# DeMux3.net
KiCad netlist of a schematic drawn in EAGLE
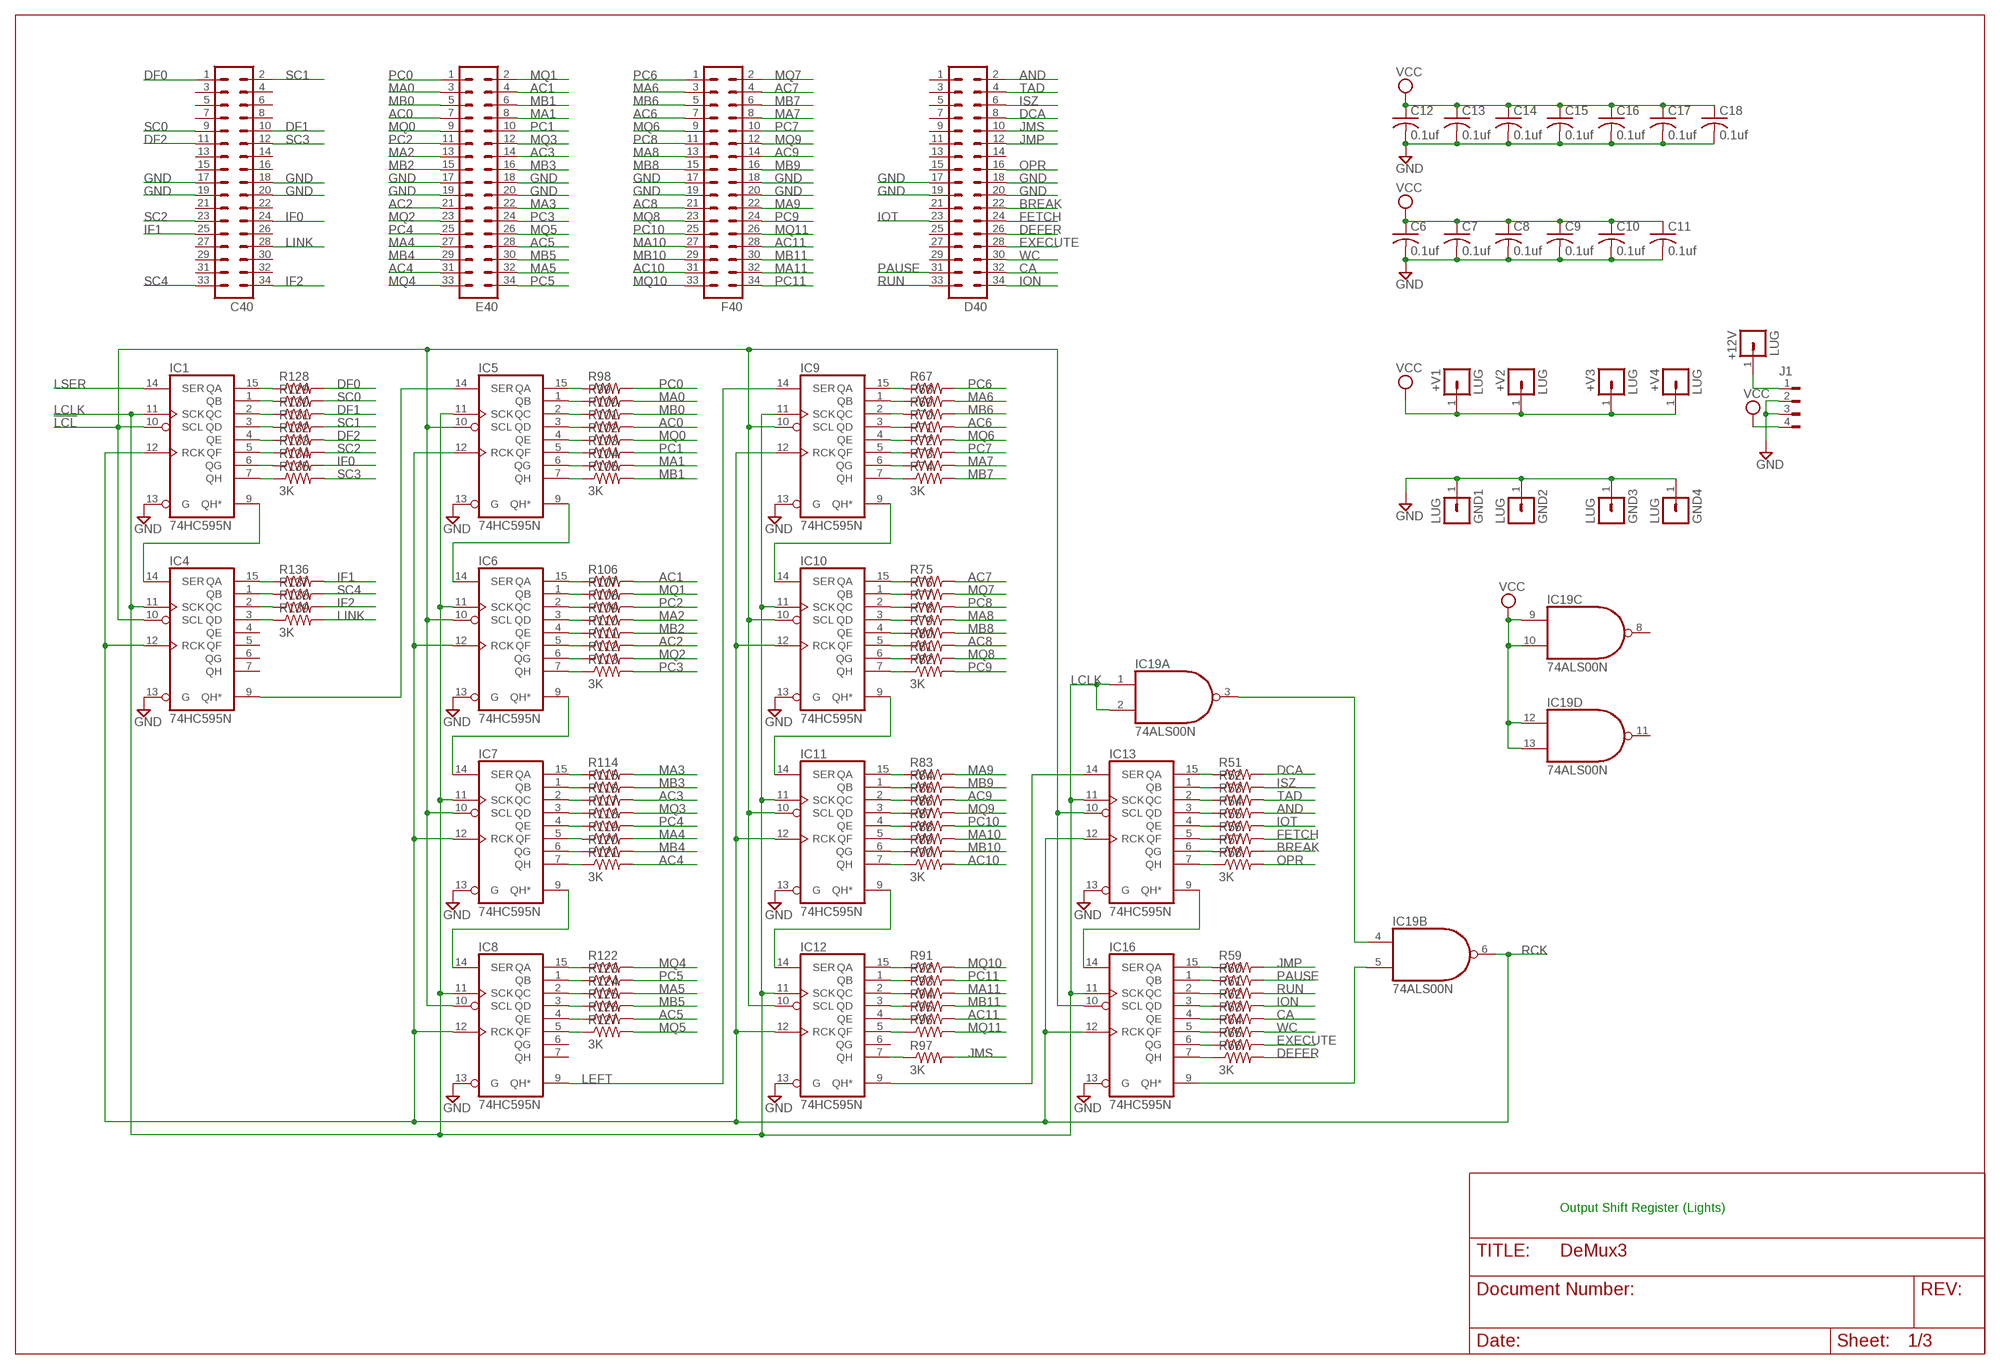
[diagram p0: schematic, sheet 1]
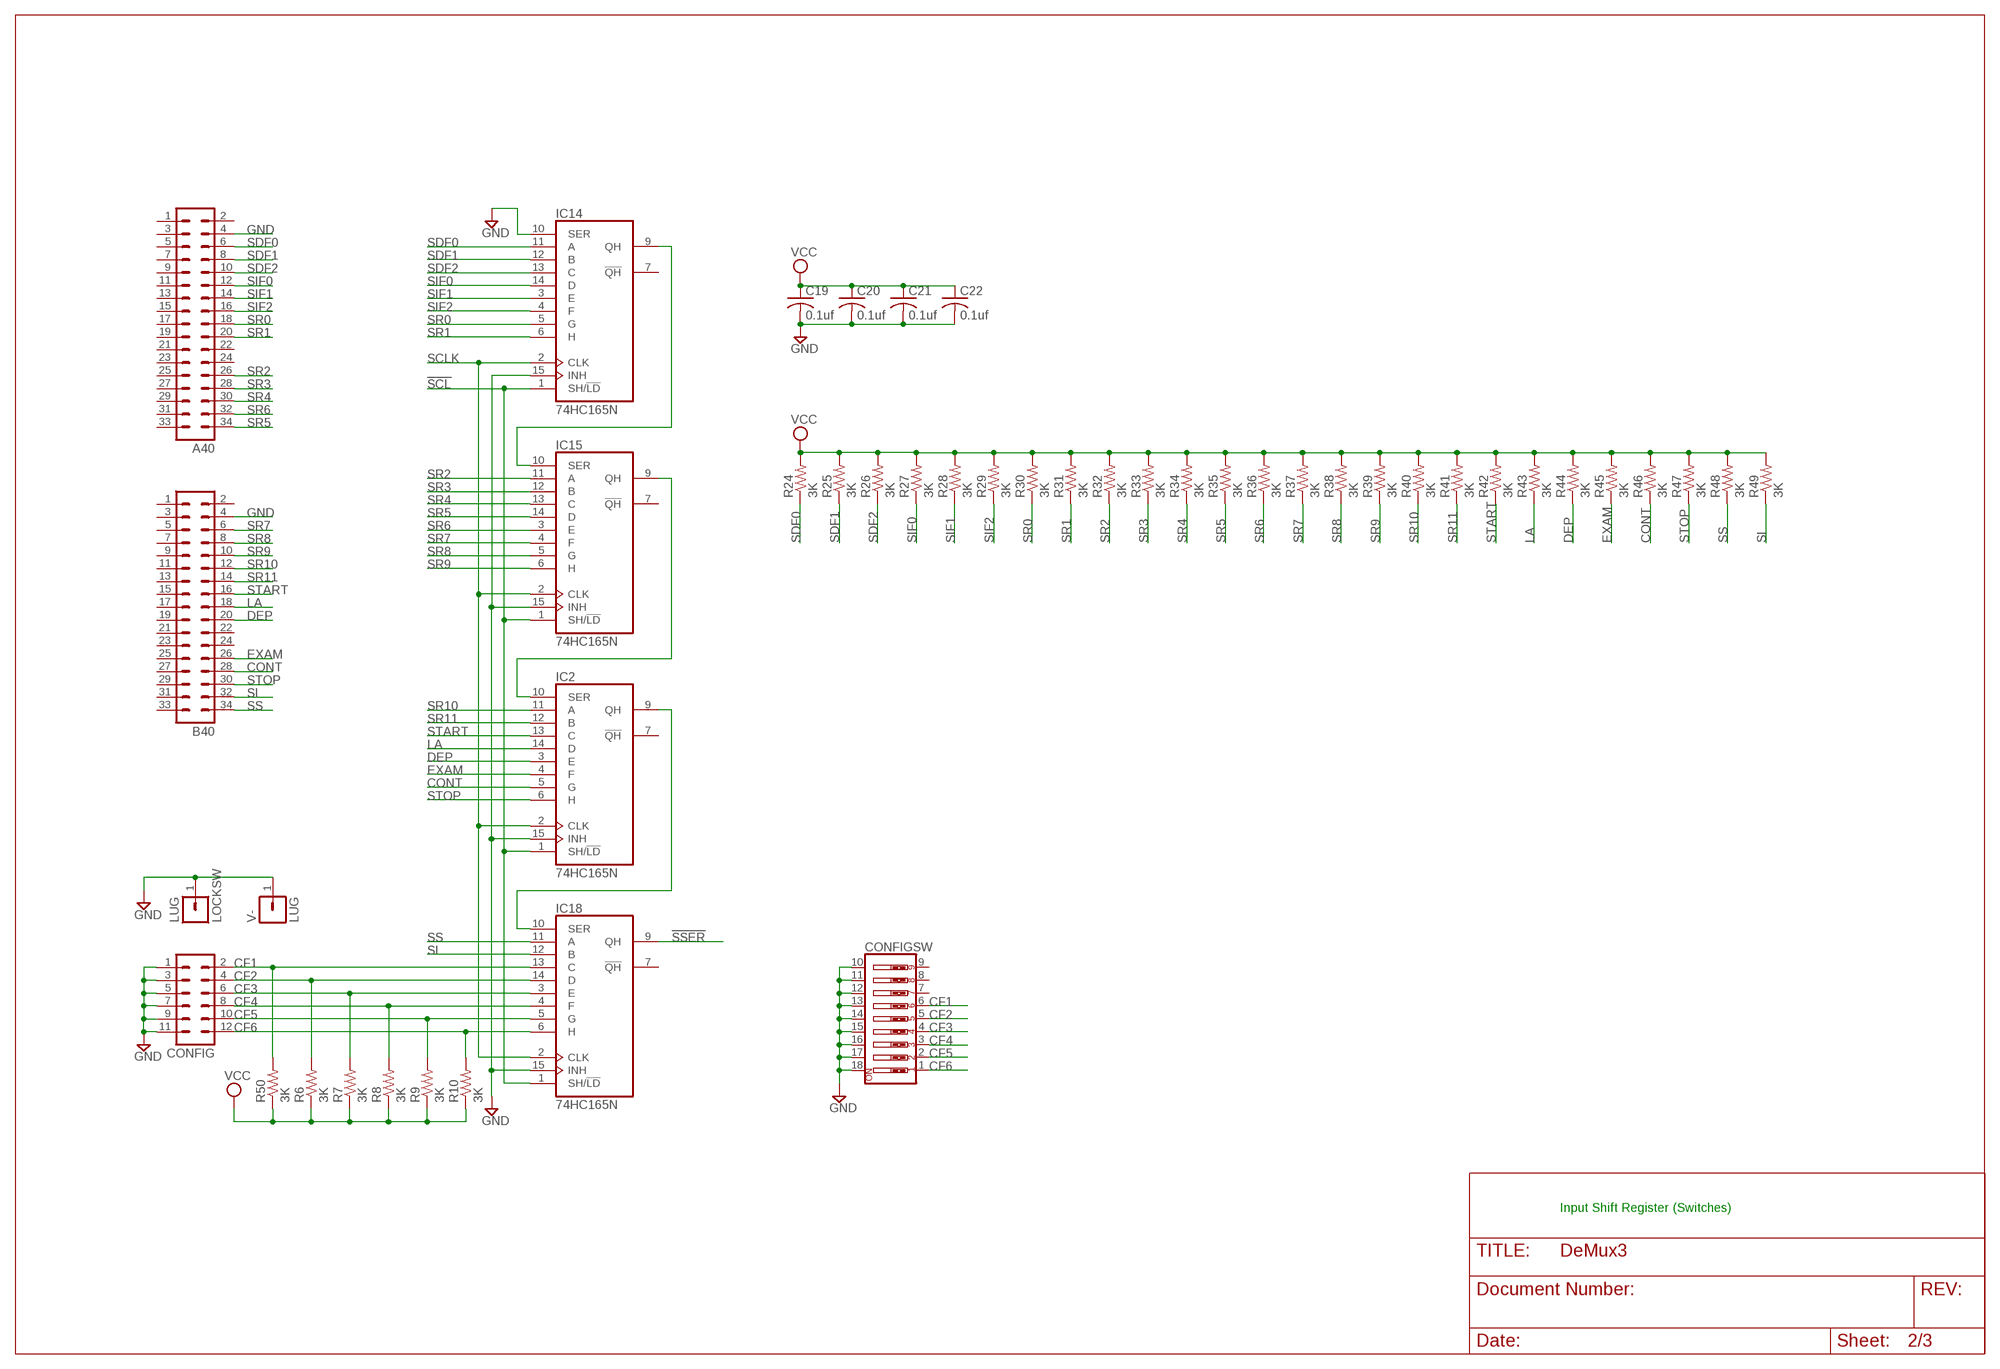
[diagram p1: schematic, sheet 2]
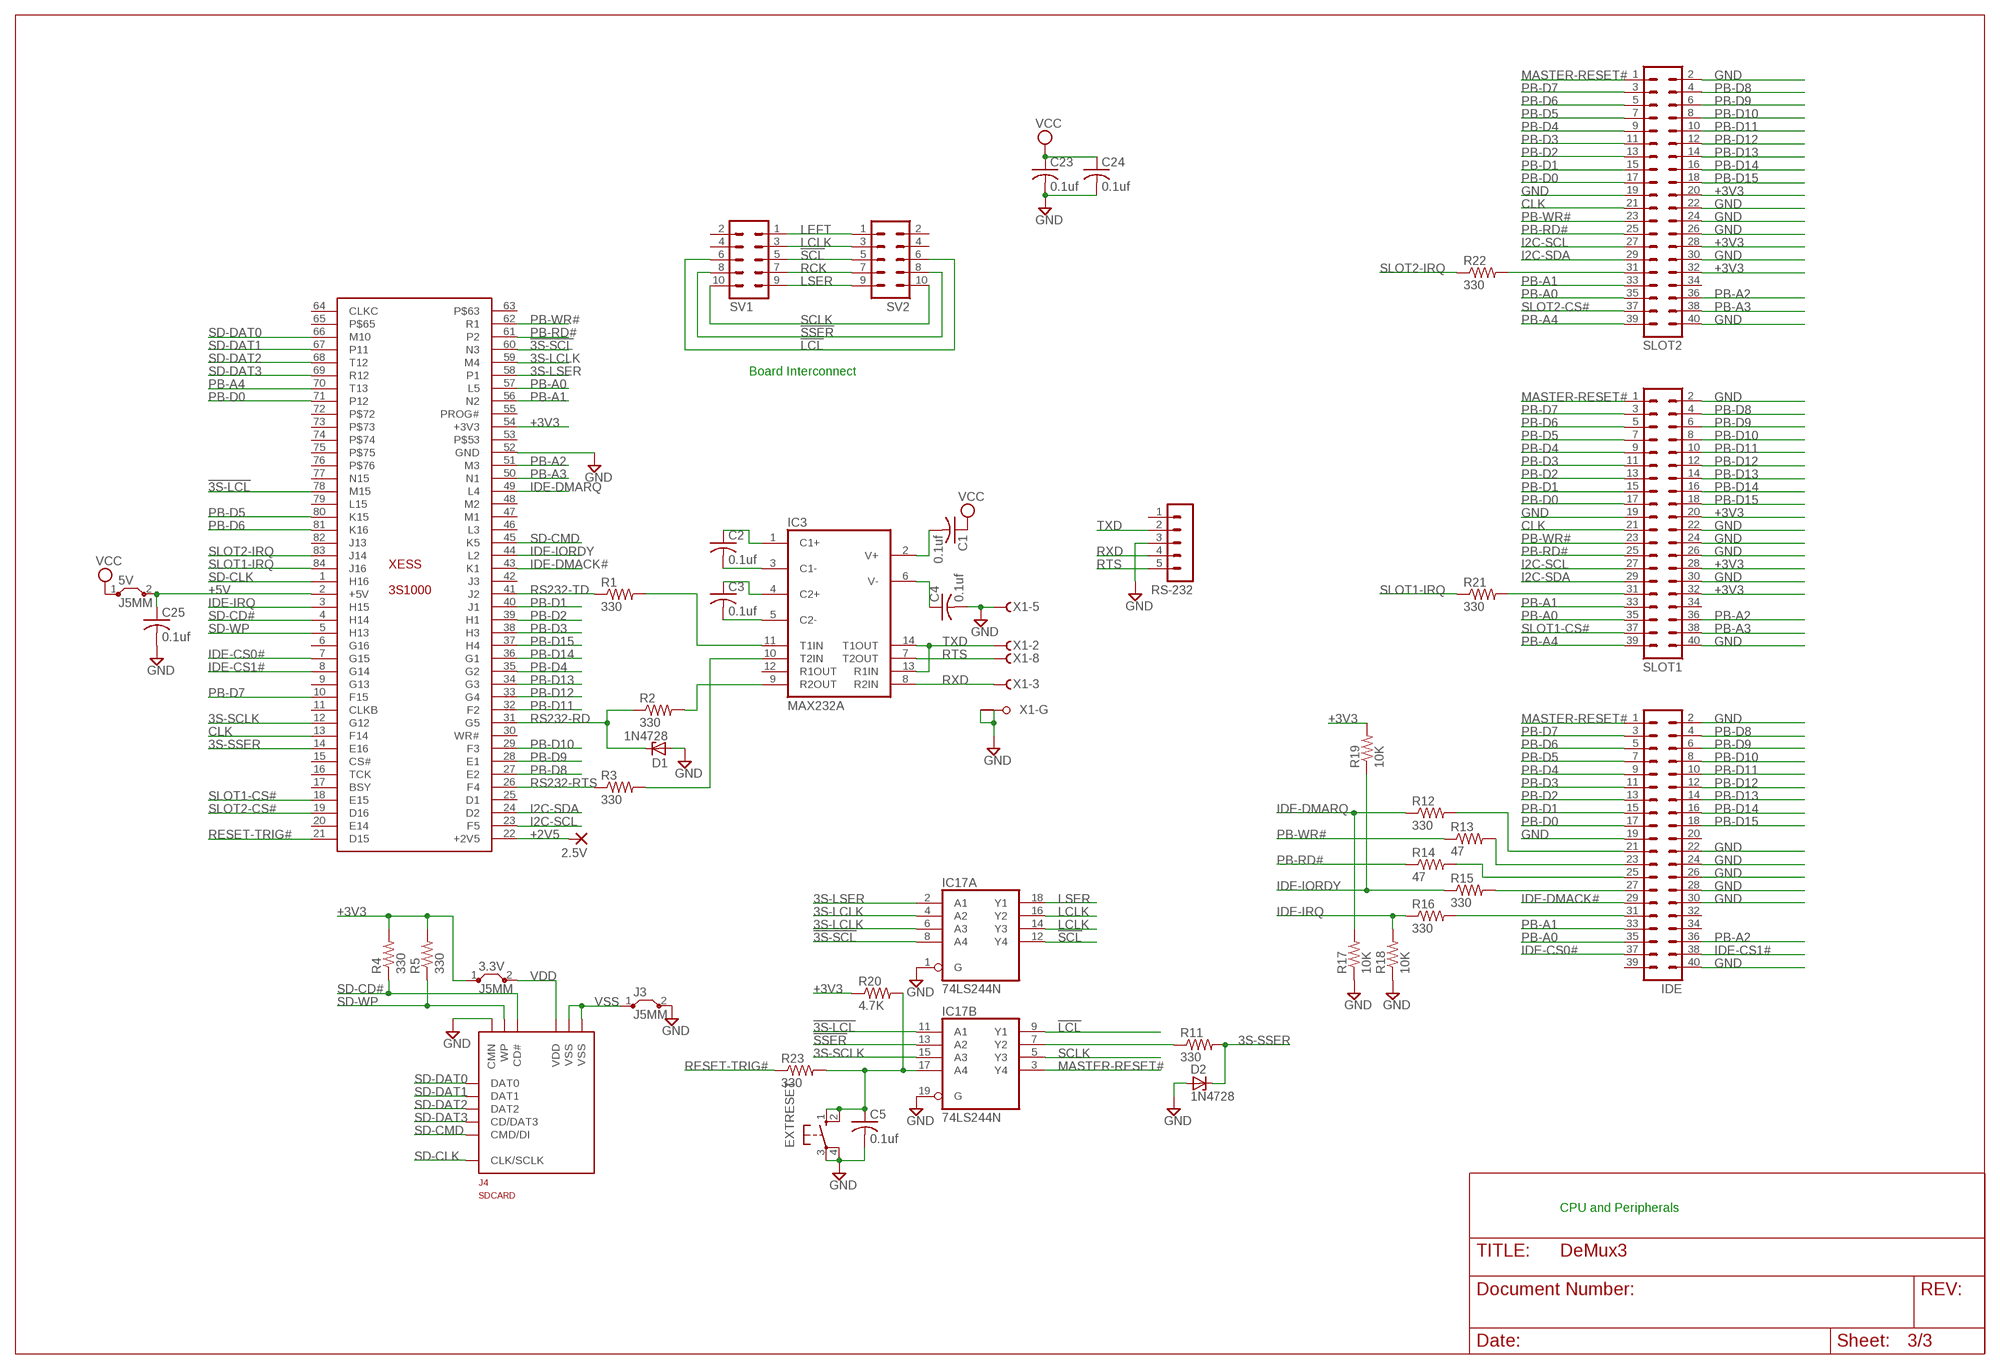
[diagram p2: schematic, sheet 3]

(export (version "E")
  (design (tool "Eeschema 10.0.6"))
  (components
    (comp (ref "2.5V")
      (value "1,6/0,8")
      (footprint "eagle-import:1,6_0,8")
      (libsource (lib "eagle-import") (part "1,6/0,8"))
    )
    (comp (ref "3.3V")
      (value "J5MM")
      (footprint "eagle-import:05")
      (libsource (lib "eagle-import") (part "J5MM"))
    )
    (comp (ref "5V")
      (value "J5MM")
      (footprint "eagle-import:05")
      (libsource (lib "eagle-import") (part "J5MM"))
    )
    (comp (ref "C1")
      (value "0.1uf")
      (footprint "eagle-import:C050-025X075")
      (libsource (lib "eagle-import") (part "C-US050-025X075"))
    )
    (comp (ref "C2")
      (value "0.1uf")
      (footprint "eagle-import:C050-025X075")
      (libsource (lib "eagle-import") (part "C-US050-025X075"))
    )
    (comp (ref "C3")
      (value "0.1uf")
      (footprint "eagle-import:C050-025X075")
      (libsource (lib "eagle-import") (part "C-US050-025X075"))
    )
    (comp (ref "C4")
      (value "0.1uf")
      (footprint "eagle-import:C050-025X075")
      (libsource (lib "eagle-import") (part "C-US050-025X075"))
    )
    (comp (ref "C5")
      (value "0.1uf")
      (footprint "eagle-import:C050-025X075")
      (libsource (lib "eagle-import") (part "C-US050-025X075"))
    )
    (comp (ref "C23")
      (value "0.1uf")
      (footprint "eagle-import:C050-025X075")
      (libsource (lib "eagle-import") (part "C-US050-025X075"))
    )
    (comp (ref "C24")
      (value "0.1uf")
      (footprint "eagle-import:C050-025X075")
      (libsource (lib "eagle-import") (part "C-US050-025X075"))
    )
    (comp (ref "C25")
      (value "0.1uf")
      (footprint "eagle-import:C050-025X075")
      (libsource (lib "eagle-import") (part "C-US050-025X075"))
    )
    (comp (ref "D1")
      (value "1N4728")
      (footprint "eagle-import:DO41Z10")
      (libsource (lib "eagle-import") (part "1N4728"))
    )
    (comp (ref "D2")
      (value "1N4728")
      (footprint "eagle-import:DO41Z10")
      (libsource (lib "eagle-import") (part "1N4728"))
    )
    (comp (ref "EXTRESET")
      (value "40-XX")
      (footprint "eagle-import:B3F-40XX")
      (fields (field (name "MF") "OMRON COMPONENTS USA") (field (name "MPN") "B3F-4000"))
      (libsource (lib "eagle-import") (part "40-XX"))
    )
    (comp (ref "IC3")
      (value "MAX232A")
      (footprint "eagle-import:DIL16")
      (fields (field (name "MF") "MAXIM") (field (name "MPN") "MAX232ACPE+"))
      (libsource (lib "eagle-import") (part "MAX232"))
    )
    (comp (ref "IC17")
      (value "74LS244N")
      (footprint "eagle-import:DIL20")
      (libsource (lib "eagle-import") (part "74244NLS"))
    )
    (comp (ref "IDE")
      (value "MA20-2")
      (footprint "eagle-import:MA20-2")
      (libsource (lib "eagle-import") (part "MA20-2"))
    )
    (comp (ref "J3")
      (value "J5MM")
      (footprint "eagle-import:05")
      (libsource (lib "eagle-import") (part "J5MM"))
    )
    (comp (ref "J4")
      (value "SDCARD")
      (footprint "eagle-import:SCDA5A")
      (libsource (lib "eagle-import") (part "SDCARD"))
    )
    (comp (ref "R1")
      (value "330")
      (footprint "eagle-import:0207_10")
      (libsource (lib "eagle-import") (part "R-US_0207/10"))
    )
    (comp (ref "R2")
      (value "330")
      (footprint "eagle-import:0207_10")
      (libsource (lib "eagle-import") (part "R-US_0207/10"))
    )
    (comp (ref "R3")
      (value "330")
      (footprint "eagle-import:0207_10")
      (libsource (lib "eagle-import") (part "R-US_0207/10"))
    )
    (comp (ref "R4")
      (value "330")
      (footprint "eagle-import:0207_10")
      (libsource (lib "eagle-import") (part "R-US_0207/10"))
    )
    (comp (ref "R5")
      (value "330")
      (footprint "eagle-import:0207_10")
      (libsource (lib "eagle-import") (part "R-US_0207/10"))
    )
    (comp (ref "R11")
      (value "330")
      (footprint "eagle-import:0207_10")
      (libsource (lib "eagle-import") (part "R-US_0207/10"))
    )
    (comp (ref "R12")
      (value "330")
      (footprint "eagle-import:0207_10")
      (libsource (lib "eagle-import") (part "R-US_0207/10"))
    )
    (comp (ref "R13")
      (value "47")
      (footprint "eagle-import:0207_10")
      (libsource (lib "eagle-import") (part "R-US_0207/10"))
    )
    (comp (ref "R14")
      (value "47")
      (footprint "eagle-import:0207_10")
      (libsource (lib "eagle-import") (part "R-US_0207/10"))
    )
    (comp (ref "R15")
      (value "330")
      (footprint "eagle-import:0207_10")
      (libsource (lib "eagle-import") (part "R-US_0207/10"))
    )
    (comp (ref "R16")
      (value "330")
      (footprint "eagle-import:0207_10")
      (libsource (lib "eagle-import") (part "R-US_0207/10"))
    )
    (comp (ref "R17")
      (value "10K")
      (footprint "eagle-import:0207_10")
      (libsource (lib "eagle-import") (part "R-US_0207/10"))
    )
    (comp (ref "R18")
      (value "10K")
      (footprint "eagle-import:0207_10")
      (libsource (lib "eagle-import") (part "R-US_0207/10"))
    )
    (comp (ref "R19")
      (value "10K")
      (footprint "eagle-import:0207_10")
      (libsource (lib "eagle-import") (part "R-US_0207/10"))
    )
    (comp (ref "R20")
      (value "4.7K")
      (footprint "eagle-import:0207_10")
      (libsource (lib "eagle-import") (part "R-US_0207/10"))
    )
    (comp (ref "R21")
      (value "330")
      (footprint "eagle-import:0207_10")
      (libsource (lib "eagle-import") (part "R-US_0207/10"))
    )
    (comp (ref "R22")
      (value "330")
      (footprint "eagle-import:0207_10")
      (libsource (lib "eagle-import") (part "R-US_0207/10"))
    )
    (comp (ref "R23")
      (value "330")
      (footprint "eagle-import:0207_10")
      (libsource (lib "eagle-import") (part "R-US_0207/10"))
    )
    (comp (ref "RS-232")
      (value "MA05-1")
      (footprint "eagle-import:MA05-1")
      (libsource (lib "eagle-import") (part "MA05-1"))
    )
    (comp (ref "SLOT1")
      (value "MA20-2")
      (footprint "eagle-import:MA20-2")
      (libsource (lib "eagle-import") (part "MA20-2"))
    )
    (comp (ref "SLOT2")
      (value "MA20-2")
      (footprint "eagle-import:MA20-2")
      (libsource (lib "eagle-import") (part "MA20-2"))
    )
    (comp (ref "SV1")
      (value "MA05-2")
      (footprint "eagle-import:MA05-2")
      (libsource (lib "eagle-import") (part "MA05-2"))
    )
    (comp (ref "SV2")
      (value "MA05-2")
      (footprint "eagle-import:MA05-2")
      (libsource (lib "eagle-import") (part "MA05-2"))
    )
    (comp (ref "X1")
      (value "F09HPS")
      (footprint "eagle-import:F09HP")
      (libsource (lib "eagle-import") (part "F09HPS"))
    )
    (comp (ref "XESS")
      (value "3S1000")
      (footprint "eagle-import:3S1000")
      (libsource (lib "eagle-import") (part "3S1000"))
    )
    (comp (ref "+12V")
      (value "LUG")
      (footprint "eagle-import:SPADELUG")
      (libsource (lib "eagle-import") (part "LUG"))
    )
    (comp (ref "+V1")
      (value "LUG")
      (footprint "eagle-import:SPADELUG")
      (libsource (lib "eagle-import") (part "LUG"))
    )
    (comp (ref "+V2")
      (value "LUG")
      (footprint "eagle-import:SPADELUG")
      (libsource (lib "eagle-import") (part "LUG"))
    )
    (comp (ref "+V3")
      (value "LUG")
      (footprint "eagle-import:SPADELUG")
      (libsource (lib "eagle-import") (part "LUG"))
    )
    (comp (ref "+V4")
      (value "LUG")
      (footprint "eagle-import:SPADELUG")
      (libsource (lib "eagle-import") (part "LUG"))
    )
    (comp (ref "C6")
      (value "0.1uf")
      (footprint "eagle-import:C050-025X075")
      (libsource (lib "eagle-import") (part "C-US050-025X075"))
    )
    (comp (ref "C7")
      (value "0.1uf")
      (footprint "eagle-import:C050-025X075")
      (libsource (lib "eagle-import") (part "C-US050-025X075"))
    )
    (comp (ref "C8")
      (value "0.1uf")
      (footprint "eagle-import:C050-025X075")
      (libsource (lib "eagle-import") (part "C-US050-025X075"))
    )
    (comp (ref "C9")
      (value "0.1uf")
      (footprint "eagle-import:C050-025X075")
      (libsource (lib "eagle-import") (part "C-US050-025X075"))
    )
    (comp (ref "C10")
      (value "0.1uf")
      (footprint "eagle-import:C050-025X075")
      (libsource (lib "eagle-import") (part "C-US050-025X075"))
    )
    (comp (ref "C11")
      (value "0.1uf")
      (footprint "eagle-import:C050-025X075")
      (libsource (lib "eagle-import") (part "C-US050-025X075"))
    )
    (comp (ref "C12")
      (value "0.1uf")
      (footprint "eagle-import:C050-025X075")
      (libsource (lib "eagle-import") (part "C-US050-025X075"))
    )
    (comp (ref "C13")
      (value "0.1uf")
      (footprint "eagle-import:C050-025X075")
      (libsource (lib "eagle-import") (part "C-US050-025X075"))
    )
    (comp (ref "C14")
      (value "0.1uf")
      (footprint "eagle-import:C050-025X075")
      (libsource (lib "eagle-import") (part "C-US050-025X075"))
    )
    (comp (ref "C15")
      (value "0.1uf")
      (footprint "eagle-import:C050-025X075")
      (libsource (lib "eagle-import") (part "C-US050-025X075"))
    )
    (comp (ref "C16")
      (value "0.1uf")
      (footprint "eagle-import:C050-025X075")
      (libsource (lib "eagle-import") (part "C-US050-025X075"))
    )
    (comp (ref "C17")
      (value "0.1uf")
      (footprint "eagle-import:C050-025X075")
      (libsource (lib "eagle-import") (part "C-US050-025X075"))
    )
    (comp (ref "C18")
      (value "0.1uf")
      (footprint "eagle-import:C050-025X075")
      (libsource (lib "eagle-import") (part "C-US050-025X075"))
    )
    (comp (ref "C40")
      (value "MA17-2")
      (footprint "eagle-import:MA17-2")
      (libsource (lib "eagle-import") (part "MA17-2"))
    )
    (comp (ref "D40")
      (value "MA17-2")
      (footprint "eagle-import:MA17-2")
      (libsource (lib "eagle-import") (part "MA17-2"))
    )
    (comp (ref "E40")
      (value "MA17-2")
      (footprint "eagle-import:MA17-2")
      (libsource (lib "eagle-import") (part "MA17-2"))
    )
    (comp (ref "F40")
      (value "MA17-2")
      (footprint "eagle-import:MA17-2")
      (libsource (lib "eagle-import") (part "MA17-2"))
    )
    (comp (ref "GND1")
      (value "LUG")
      (footprint "eagle-import:SPADELUG")
      (libsource (lib "eagle-import") (part "LUG"))
    )
    (comp (ref "GND2")
      (value "LUG")
      (footprint "eagle-import:SPADELUG")
      (libsource (lib "eagle-import") (part "LUG"))
    )
    (comp (ref "GND3")
      (value "LUG")
      (footprint "eagle-import:SPADELUG")
      (libsource (lib "eagle-import") (part "LUG"))
    )
    (comp (ref "GND4")
      (value "LUG")
      (footprint "eagle-import:SPADELUG")
      (libsource (lib "eagle-import") (part "LUG"))
    )
    (comp (ref "IC1")
      (value "74HC595N")
      (footprint "eagle-import:DIL16")
      (libsource (lib "eagle-import") (part "74595NLS"))
    )
    (comp (ref "IC4")
      (value "74HC595N")
      (footprint "eagle-import:DIL16")
      (libsource (lib "eagle-import") (part "74595NLS"))
    )
    (comp (ref "IC5")
      (value "74HC595N")
      (footprint "eagle-import:DIL16")
      (libsource (lib "eagle-import") (part "74595NLS"))
    )
    (comp (ref "IC6")
      (value "74HC595N")
      (footprint "eagle-import:DIL16")
      (libsource (lib "eagle-import") (part "74595NLS"))
    )
    (comp (ref "IC7")
      (value "74HC595N")
      (footprint "eagle-import:DIL16")
      (libsource (lib "eagle-import") (part "74595NLS"))
    )
    (comp (ref "IC8")
      (value "74HC595N")
      (footprint "eagle-import:DIL16")
      (libsource (lib "eagle-import") (part "74595NLS"))
    )
    (comp (ref "IC9")
      (value "74HC595N")
      (footprint "eagle-import:DIL16")
      (libsource (lib "eagle-import") (part "74595NLS"))
    )
    (comp (ref "IC10")
      (value "74HC595N")
      (footprint "eagle-import:DIL16")
      (libsource (lib "eagle-import") (part "74595NLS"))
    )
    (comp (ref "IC11")
      (value "74HC595N")
      (footprint "eagle-import:DIL16")
      (libsource (lib "eagle-import") (part "74595NLS"))
    )
    (comp (ref "IC12")
      (value "74HC595N")
      (footprint "eagle-import:DIL16")
      (libsource (lib "eagle-import") (part "74595NLS"))
    )
    (comp (ref "IC13")
      (value "74HC595N")
      (footprint "eagle-import:DIL16")
      (libsource (lib "eagle-import") (part "74595NLS"))
    )
    (comp (ref "IC16")
      (value "74HC595N")
      (footprint "eagle-import:DIL16")
      (libsource (lib "eagle-import") (part "74595NLS"))
    )
    (comp (ref "IC19")
      (value "74ALS00N")
      (footprint "eagle-import:DIL14")
      (libsource (lib "eagle-import") (part "7400NALS"))
    )
    (comp (ref "J1")
      (value "FLOPPY-4")
      (footprint "eagle-import:FLOPPY-4")
      (libsource (lib "eagle-import") (part "FLOPPY-4"))
    )
    (comp (ref "R51")
      (value "R-US_0207/10")
      (footprint "eagle-import:0207_10")
      (libsource (lib "eagle-import") (part "R-US_0207/10"))
    )
    (comp (ref "R52")
      (value "R-US_0207/10")
      (footprint "eagle-import:0207_10")
      (libsource (lib "eagle-import") (part "R-US_0207/10"))
    )
    (comp (ref "R53")
      (value "R-US_0207/10")
      (footprint "eagle-import:0207_10")
      (libsource (lib "eagle-import") (part "R-US_0207/10"))
    )
    (comp (ref "R54")
      (value "R-US_0207/10")
      (footprint "eagle-import:0207_10")
      (libsource (lib "eagle-import") (part "R-US_0207/10"))
    )
    (comp (ref "R55")
      (value "R-US_0207/10")
      (footprint "eagle-import:0207_10")
      (libsource (lib "eagle-import") (part "R-US_0207/10"))
    )
    (comp (ref "R56")
      (value "R-US_0207/10")
      (footprint "eagle-import:0207_10")
      (libsource (lib "eagle-import") (part "R-US_0207/10"))
    )
    (comp (ref "R57")
      (value "R-US_0207/10")
      (footprint "eagle-import:0207_10")
      (libsource (lib "eagle-import") (part "R-US_0207/10"))
    )
    (comp (ref "R58")
      (value "3K")
      (footprint "eagle-import:0207_10")
      (libsource (lib "eagle-import") (part "R-US_0207/10"))
    )
    (comp (ref "R59")
      (value "R-US_0207/10")
      (footprint "eagle-import:0207_10")
      (libsource (lib "eagle-import") (part "R-US_0207/10"))
    )
    (comp (ref "R60")
      (value "R-US_0207/10")
      (footprint "eagle-import:0207_10")
      (libsource (lib "eagle-import") (part "R-US_0207/10"))
    )
    (comp (ref "R61")
      (value "R-US_0207/10")
      (footprint "eagle-import:0207_10")
      (libsource (lib "eagle-import") (part "R-US_0207/10"))
    )
    (comp (ref "R62")
      (value "R-US_0207/10")
      (footprint "eagle-import:0207_10")
      (libsource (lib "eagle-import") (part "R-US_0207/10"))
    )
    (comp (ref "R63")
      (value "R-US_0207/10")
      (footprint "eagle-import:0207_10")
      (libsource (lib "eagle-import") (part "R-US_0207/10"))
    )
    (comp (ref "R64")
      (value "R-US_0207/10")
      (footprint "eagle-import:0207_10")
      (libsource (lib "eagle-import") (part "R-US_0207/10"))
    )
    (comp (ref "R65")
      (value "R-US_0207/10")
      (footprint "eagle-import:0207_10")
      (libsource (lib "eagle-import") (part "R-US_0207/10"))
    )
    (comp (ref "R66")
      (value "3K")
      (footprint "eagle-import:0207_10")
      (libsource (lib "eagle-import") (part "R-US_0207/10"))
    )
    (comp (ref "R67")
      (value "R-US_0207/10")
      (footprint "eagle-import:0207_10")
      (libsource (lib "eagle-import") (part "R-US_0207/10"))
    )
    (comp (ref "R68")
      (value "R-US_0207/10")
      (footprint "eagle-import:0207_10")
      (libsource (lib "eagle-import") (part "R-US_0207/10"))
    )
    (comp (ref "R69")
      (value "R-US_0207/10")
      (footprint "eagle-import:0207_10")
      (libsource (lib "eagle-import") (part "R-US_0207/10"))
    )
    (comp (ref "R70")
      (value "R-US_0207/10")
      (footprint "eagle-import:0207_10")
      (libsource (lib "eagle-import") (part "R-US_0207/10"))
    )
    (comp (ref "R71")
      (value "R-US_0207/10")
      (footprint "eagle-import:0207_10")
      (libsource (lib "eagle-import") (part "R-US_0207/10"))
    )
    (comp (ref "R72")
      (value "R-US_0207/10")
      (footprint "eagle-import:0207_10")
      (libsource (lib "eagle-import") (part "R-US_0207/10"))
    )
    (comp (ref "R73")
      (value "R-US_0207/10")
      (footprint "eagle-import:0207_10")
      (libsource (lib "eagle-import") (part "R-US_0207/10"))
    )
    (comp (ref "R74")
      (value "3K")
      (footprint "eagle-import:0207_10")
      (libsource (lib "eagle-import") (part "R-US_0207/10"))
    )
    (comp (ref "R75")
      (value "R-US_0207/10")
      (footprint "eagle-import:0207_10")
      (libsource (lib "eagle-import") (part "R-US_0207/10"))
    )
    (comp (ref "R76")
      (value "R-US_0207/10")
      (footprint "eagle-import:0207_10")
      (libsource (lib "eagle-import") (part "R-US_0207/10"))
    )
    (comp (ref "R77")
      (value "R-US_0207/10")
      (footprint "eagle-import:0207_10")
      (libsource (lib "eagle-import") (part "R-US_0207/10"))
    )
    (comp (ref "R78")
      (value "R-US_0207/10")
      (footprint "eagle-import:0207_10")
      (libsource (lib "eagle-import") (part "R-US_0207/10"))
    )
    (comp (ref "R79")
      (value "R-US_0207/10")
      (footprint "eagle-import:0207_10")
      (libsource (lib "eagle-import") (part "R-US_0207/10"))
    )
    (comp (ref "R80")
      (value "R-US_0207/10")
      (footprint "eagle-import:0207_10")
      (libsource (lib "eagle-import") (part "R-US_0207/10"))
    )
    (comp (ref "R81")
      (value "R-US_0207/10")
      (footprint "eagle-import:0207_10")
      (libsource (lib "eagle-import") (part "R-US_0207/10"))
    )
    (comp (ref "R82")
      (value "3K")
      (footprint "eagle-import:0207_10")
      (libsource (lib "eagle-import") (part "R-US_0207/10"))
    )
    (comp (ref "R83")
      (value "R-US_0207/10")
      (footprint "eagle-import:0207_10")
      (libsource (lib "eagle-import") (part "R-US_0207/10"))
    )
    (comp (ref "R84")
      (value "R-US_0207/10")
      (footprint "eagle-import:0207_10")
      (libsource (lib "eagle-import") (part "R-US_0207/10"))
    )
    (comp (ref "R85")
      (value "R-US_0207/10")
      (footprint "eagle-import:0207_10")
      (libsource (lib "eagle-import") (part "R-US_0207/10"))
    )
    (comp (ref "R86")
      (value "R-US_0207/10")
      (footprint "eagle-import:0207_10")
      (libsource (lib "eagle-import") (part "R-US_0207/10"))
    )
    (comp (ref "R87")
      (value "R-US_0207/10")
      (footprint "eagle-import:0207_10")
      (libsource (lib "eagle-import") (part "R-US_0207/10"))
    )
    (comp (ref "R88")
      (value "R-US_0207/10")
      (footprint "eagle-import:0207_10")
      (libsource (lib "eagle-import") (part "R-US_0207/10"))
    )
    (comp (ref "R89")
      (value "R-US_0207/10")
      (footprint "eagle-import:0207_10")
      (libsource (lib "eagle-import") (part "R-US_0207/10"))
    )
    (comp (ref "R90")
      (value "3K")
      (footprint "eagle-import:0207_10")
      (libsource (lib "eagle-import") (part "R-US_0207/10"))
    )
    (comp (ref "R91")
      (value "R-US_0207/10")
      (footprint "eagle-import:0207_10")
      (libsource (lib "eagle-import") (part "R-US_0207/10"))
    )
    (comp (ref "R92")
      (value "R-US_0207/10")
      (footprint "eagle-import:0207_10")
      (libsource (lib "eagle-import") (part "R-US_0207/10"))
    )
    (comp (ref "R93")
      (value "R-US_0207/10")
      (footprint "eagle-import:0207_10")
      (libsource (lib "eagle-import") (part "R-US_0207/10"))
    )
    (comp (ref "R94")
      (value "R-US_0207/10")
      (footprint "eagle-import:0207_10")
      (libsource (lib "eagle-import") (part "R-US_0207/10"))
    )
    (comp (ref "R95")
      (value "R-US_0207/10")
      (footprint "eagle-import:0207_10")
      (libsource (lib "eagle-import") (part "R-US_0207/10"))
    )
    (comp (ref "R96")
      (value "R-US_0207/10")
      (footprint "eagle-import:0207_10")
      (libsource (lib "eagle-import") (part "R-US_0207/10"))
    )
    (comp (ref "R97")
      (value "3K")
      (footprint "eagle-import:0207_10")
      (libsource (lib "eagle-import") (part "R-US_0207/10"))
    )
    (comp (ref "R98")
      (value "R-US_0207/10")
      (footprint "eagle-import:0207_10")
      (libsource (lib "eagle-import") (part "R-US_0207/10"))
    )
    (comp (ref "R99")
      (value "R-US_0207/10")
      (footprint "eagle-import:0207_10")
      (libsource (lib "eagle-import") (part "R-US_0207/10"))
    )
    (comp (ref "R100")
      (value "R-US_0207/10")
      (footprint "eagle-import:0207_10")
      (libsource (lib "eagle-import") (part "R-US_0207/10"))
    )
    (comp (ref "R101")
      (value "R-US_0207/10")
      (footprint "eagle-import:0207_10")
      (libsource (lib "eagle-import") (part "R-US_0207/10"))
    )
    (comp (ref "R102")
      (value "R-US_0207/10")
      (footprint "eagle-import:0207_10")
      (libsource (lib "eagle-import") (part "R-US_0207/10"))
    )
    (comp (ref "R103")
      (value "R-US_0207/10")
      (footprint "eagle-import:0207_10")
      (libsource (lib "eagle-import") (part "R-US_0207/10"))
    )
    (comp (ref "R104")
      (value "R-US_0207/10")
      (footprint "eagle-import:0207_10")
      (libsource (lib "eagle-import") (part "R-US_0207/10"))
    )
    (comp (ref "R105")
      (value "3K")
      (footprint "eagle-import:0207_10")
      (libsource (lib "eagle-import") (part "R-US_0207/10"))
    )
    (comp (ref "R106")
      (value "R-US_0207/10")
      (footprint "eagle-import:0207_10")
      (libsource (lib "eagle-import") (part "R-US_0207/10"))
    )
    (comp (ref "R107")
      (value "R-US_0207/10")
      (footprint "eagle-import:0207_10")
      (libsource (lib "eagle-import") (part "R-US_0207/10"))
    )
    (comp (ref "R108")
      (value "R-US_0207/10")
      (footprint "eagle-import:0207_10")
      (libsource (lib "eagle-import") (part "R-US_0207/10"))
    )
    (comp (ref "R109")
      (value "R-US_0207/10")
      (footprint "eagle-import:0207_10")
      (libsource (lib "eagle-import") (part "R-US_0207/10"))
    )
    (comp (ref "R110")
      (value "R-US_0207/10")
      (footprint "eagle-import:0207_10")
      (libsource (lib "eagle-import") (part "R-US_0207/10"))
    )
    (comp (ref "R111")
      (value "R-US_0207/10")
      (footprint "eagle-import:0207_10")
      (libsource (lib "eagle-import") (part "R-US_0207/10"))
    )
    (comp (ref "R112")
      (value "R-US_0207/10")
      (footprint "eagle-import:0207_10")
      (libsource (lib "eagle-import") (part "R-US_0207/10"))
    )
    (comp (ref "R113")
      (value "3K")
      (footprint "eagle-import:0207_10")
      (libsource (lib "eagle-import") (part "R-US_0207/10"))
    )
    (comp (ref "R114")
      (value "R-US_0207/10")
      (footprint "eagle-import:0207_10")
      (libsource (lib "eagle-import") (part "R-US_0207/10"))
    )
    (comp (ref "R115")
      (value "R-US_0207/10")
      (footprint "eagle-import:0207_10")
      (libsource (lib "eagle-import") (part "R-US_0207/10"))
    )
    (comp (ref "R116")
      (value "R-US_0207/10")
      (footprint "eagle-import:0207_10")
      (libsource (lib "eagle-import") (part "R-US_0207/10"))
    )
    (comp (ref "R117")
      (value "R-US_0207/10")
      (footprint "eagle-import:0207_10")
      (libsource (lib "eagle-import") (part "R-US_0207/10"))
    )
    (comp (ref "R118")
      (value "R-US_0207/10")
      (footprint "eagle-import:0207_10")
      (libsource (lib "eagle-import") (part "R-US_0207/10"))
    )
    (comp (ref "R119")
      (value "R-US_0207/10")
      (footprint "eagle-import:0207_10")
      (libsource (lib "eagle-import") (part "R-US_0207/10"))
    )
    (comp (ref "R120")
      (value "R-US_0207/10")
      (footprint "eagle-import:0207_10")
      (libsource (lib "eagle-import") (part "R-US_0207/10"))
    )
    (comp (ref "R121")
      (value "3K")
      (footprint "eagle-import:0207_10")
      (libsource (lib "eagle-import") (part "R-US_0207/10"))
    )
    (comp (ref "R122")
      (value "R-US_0207/10")
      (footprint "eagle-import:0207_10")
      (libsource (lib "eagle-import") (part "R-US_0207/10"))
    )
    (comp (ref "R123")
      (value "R-US_0207/10")
      (footprint "eagle-import:0207_10")
      (libsource (lib "eagle-import") (part "R-US_0207/10"))
    )
    (comp (ref "R124")
      (value "R-US_0207/10")
      (footprint "eagle-import:0207_10")
      (libsource (lib "eagle-import") (part "R-US_0207/10"))
    )
    (comp (ref "R125")
      (value "R-US_0207/10")
      (footprint "eagle-import:0207_10")
      (libsource (lib "eagle-import") (part "R-US_0207/10"))
    )
    (comp (ref "R126")
      (value "R-US_0207/10")
      (footprint "eagle-import:0207_10")
      (libsource (lib "eagle-import") (part "R-US_0207/10"))
    )
    (comp (ref "R127")
      (value "3K")
      (footprint "eagle-import:0207_10")
      (libsource (lib "eagle-import") (part "R-US_0207/10"))
    )
    (comp (ref "R128")
      (value "R-US_0207/10")
      (footprint "eagle-import:0207_10")
      (libsource (lib "eagle-import") (part "R-US_0207/10"))
    )
    (comp (ref "R129")
      (value "R-US_0207/10")
      (footprint "eagle-import:0207_10")
      (libsource (lib "eagle-import") (part "R-US_0207/10"))
    )
    (comp (ref "R130")
      (value "R-US_0207/10")
      (footprint "eagle-import:0207_10")
      (libsource (lib "eagle-import") (part "R-US_0207/10"))
    )
    (comp (ref "R131")
      (value "R-US_0207/10")
      (footprint "eagle-import:0207_10")
      (libsource (lib "eagle-import") (part "R-US_0207/10"))
    )
    (comp (ref "R132")
      (value "R-US_0207/10")
      (footprint "eagle-import:0207_10")
      (libsource (lib "eagle-import") (part "R-US_0207/10"))
    )
    (comp (ref "R133")
      (value "R-US_0207/10")
      (footprint "eagle-import:0207_10")
      (libsource (lib "eagle-import") (part "R-US_0207/10"))
    )
    (comp (ref "R134")
      (value "R-US_0207/10")
      (footprint "eagle-import:0207_10")
      (libsource (lib "eagle-import") (part "R-US_0207/10"))
    )
    (comp (ref "R135")
      (value "3K")
      (footprint "eagle-import:0207_10")
      (libsource (lib "eagle-import") (part "R-US_0207/10"))
    )
    (comp (ref "R136")
      (value "R-US_0207/10")
      (footprint "eagle-import:0207_10")
      (libsource (lib "eagle-import") (part "R-US_0207/10"))
    )
    (comp (ref "R137")
      (value "R-US_0207/10")
      (footprint "eagle-import:0207_10")
      (libsource (lib "eagle-import") (part "R-US_0207/10"))
    )
    (comp (ref "R138")
      (value "R-US_0207/10")
      (footprint "eagle-import:0207_10")
      (libsource (lib "eagle-import") (part "R-US_0207/10"))
    )
    (comp (ref "R139")
      (value "3K")
      (footprint "eagle-import:0207_10")
      (libsource (lib "eagle-import") (part "R-US_0207/10"))
    )
    (comp (ref "A40")
      (value "MA17-2")
      (footprint "eagle-import:MA17-2")
      (libsource (lib "eagle-import") (part "MA17-2"))
    )
    (comp (ref "B40")
      (value "MA17-2")
      (footprint "eagle-import:MA17-2")
      (libsource (lib "eagle-import") (part "MA17-2"))
    )
    (comp (ref "C19")
      (value "0.1uf")
      (footprint "eagle-import:C050-025X075")
      (libsource (lib "eagle-import") (part "C-US050-025X075"))
    )
    (comp (ref "C20")
      (value "0.1uf")
      (footprint "eagle-import:C050-025X075")
      (libsource (lib "eagle-import") (part "C-US050-025X075"))
    )
    (comp (ref "C21")
      (value "0.1uf")
      (footprint "eagle-import:C050-025X075")
      (libsource (lib "eagle-import") (part "C-US050-025X075"))
    )
    (comp (ref "C22")
      (value "0.1uf")
      (footprint "eagle-import:C050-025X075")
      (libsource (lib "eagle-import") (part "C-US050-025X075"))
    )
    (comp (ref "CONFIG")
      (value "MA06-2")
      (footprint "eagle-import:MA06-2")
      (libsource (lib "eagle-import") (part "MA06-2"))
    )
    (comp (ref "CONFIGSW")
      (value "SW_DIP-9")
      (footprint "eagle-import:EDG-09")
      (libsource (lib "eagle-import") (part "SW_DIP-9"))
    )
    (comp (ref "IC2")
      (value "74HC165N")
      (footprint "eagle-import:DIL16")
      (libsource (lib "eagle-import") (part "74165NLS"))
    )
    (comp (ref "IC14")
      (value "74HC165N")
      (footprint "eagle-import:DIL16")
      (libsource (lib "eagle-import") (part "74165NLS"))
    )
    (comp (ref "IC15")
      (value "74HC165N")
      (footprint "eagle-import:DIL16")
      (libsource (lib "eagle-import") (part "74165NLS"))
    )
    (comp (ref "IC18")
      (value "74HC165N")
      (footprint "eagle-import:DIL16")
      (libsource (lib "eagle-import") (part "74165NLS"))
    )
    (comp (ref "LOCKSW")
      (value "LUG")
      (footprint "eagle-import:SPADELUG")
      (libsource (lib "eagle-import") (part "LUG"))
    )
    (comp (ref "R6")
      (value "3K")
      (footprint "eagle-import:0207_10")
      (libsource (lib "eagle-import") (part "R-US_0207/10"))
    )
    (comp (ref "R7")
      (value "3K")
      (footprint "eagle-import:0207_10")
      (libsource (lib "eagle-import") (part "R-US_0207/10"))
    )
    (comp (ref "R8")
      (value "3K")
      (footprint "eagle-import:0207_10")
      (libsource (lib "eagle-import") (part "R-US_0207/10"))
    )
    (comp (ref "R9")
      (value "3K")
      (footprint "eagle-import:0207_10")
      (libsource (lib "eagle-import") (part "R-US_0207/10"))
    )
    (comp (ref "R10")
      (value "3K")
      (footprint "eagle-import:0207_10")
      (libsource (lib "eagle-import") (part "R-US_0207/10"))
    )
    (comp (ref "R24")
      (value "3K")
      (footprint "eagle-import:0207_10")
      (libsource (lib "eagle-import") (part "R-US_0207/10"))
    )
    (comp (ref "R25")
      (value "3K")
      (footprint "eagle-import:0207_10")
      (libsource (lib "eagle-import") (part "R-US_0207/10"))
    )
    (comp (ref "R26")
      (value "3K")
      (footprint "eagle-import:0207_10")
      (libsource (lib "eagle-import") (part "R-US_0207/10"))
    )
    (comp (ref "R27")
      (value "3K")
      (footprint "eagle-import:0207_10")
      (libsource (lib "eagle-import") (part "R-US_0207/10"))
    )
    (comp (ref "R28")
      (value "3K")
      (footprint "eagle-import:0207_10")
      (libsource (lib "eagle-import") (part "R-US_0207/10"))
    )
    (comp (ref "R29")
      (value "3K")
      (footprint "eagle-import:0207_10")
      (libsource (lib "eagle-import") (part "R-US_0207/10"))
    )
    (comp (ref "R30")
      (value "3K")
      (footprint "eagle-import:0207_10")
      (libsource (lib "eagle-import") (part "R-US_0207/10"))
    )
    (comp (ref "R31")
      (value "3K")
      (footprint "eagle-import:0207_10")
      (libsource (lib "eagle-import") (part "R-US_0207/10"))
    )
    (comp (ref "R32")
      (value "3K")
      (footprint "eagle-import:0207_10")
      (libsource (lib "eagle-import") (part "R-US_0207/10"))
    )
    (comp (ref "R33")
      (value "3K")
      (footprint "eagle-import:0207_10")
      (libsource (lib "eagle-import") (part "R-US_0207/10"))
    )
    (comp (ref "R34")
      (value "3K")
      (footprint "eagle-import:0207_10")
      (libsource (lib "eagle-import") (part "R-US_0207/10"))
    )
    (comp (ref "R35")
      (value "3K")
      (footprint "eagle-import:0207_10")
      (libsource (lib "eagle-import") (part "R-US_0207/10"))
    )
    (comp (ref "R36")
      (value "3K")
      (footprint "eagle-import:0207_10")
      (libsource (lib "eagle-import") (part "R-US_0207/10"))
    )
    (comp (ref "R37")
      (value "3K")
      (footprint "eagle-import:0207_10")
      (libsource (lib "eagle-import") (part "R-US_0207/10"))
    )
    (comp (ref "R38")
      (value "3K")
      (footprint "eagle-import:0207_10")
      (libsource (lib "eagle-import") (part "R-US_0207/10"))
    )
    (comp (ref "R39")
      (value "3K")
      (footprint "eagle-import:0207_10")
      (libsource (lib "eagle-import") (part "R-US_0207/10"))
    )
    (comp (ref "R40")
      (value "3K")
      (footprint "eagle-import:0207_10")
      (libsource (lib "eagle-import") (part "R-US_0207/10"))
    )
    (comp (ref "R41")
      (value "3K")
      (footprint "eagle-import:0207_10")
      (libsource (lib "eagle-import") (part "R-US_0207/10"))
    )
    (comp (ref "R42")
      (value "3K")
      (footprint "eagle-import:0207_10")
      (libsource (lib "eagle-import") (part "R-US_0207/10"))
    )
    (comp (ref "R43")
      (value "3K")
      (footprint "eagle-import:0207_10")
      (libsource (lib "eagle-import") (part "R-US_0207/10"))
    )
    (comp (ref "R44")
      (value "3K")
      (footprint "eagle-import:0207_10")
      (libsource (lib "eagle-import") (part "R-US_0207/10"))
    )
    (comp (ref "R45")
      (value "3K")
      (footprint "eagle-import:0207_10")
      (libsource (lib "eagle-import") (part "R-US_0207/10"))
    )
    (comp (ref "R46")
      (value "3K")
      (footprint "eagle-import:0207_10")
      (libsource (lib "eagle-import") (part "R-US_0207/10"))
    )
    (comp (ref "R47")
      (value "3K")
      (footprint "eagle-import:0207_10")
      (libsource (lib "eagle-import") (part "R-US_0207/10"))
    )
    (comp (ref "R48")
      (value "3K")
      (footprint "eagle-import:0207_10")
      (libsource (lib "eagle-import") (part "R-US_0207/10"))
    )
    (comp (ref "R49")
      (value "3K")
      (footprint "eagle-import:0207_10")
      (libsource (lib "eagle-import") (part "R-US_0207/10"))
    )
    (comp (ref "R50")
      (value "3K")
      (footprint "eagle-import:0207_10")
      (libsource (lib "eagle-import") (part "R-US_0207/10"))
    )
    (comp (ref "V-")
      (value "LUG")
      (footprint "eagle-import:SPADELUG")
      (libsource (lib "eagle-import") (part "LUG"))
    )
  )
  (nets
    (net (code "1") (name "+2V5") (class "Default")
      (node (ref "2.5V") (pin "1") (pinfunction "P_1") (pintype "passive"))
      (node (ref "XESS") (pin "22") (pinfunction "+2V5_22") (pintype "power_in"))
    )
    (net (code "2") (name "+3V3") (class "Default")
      (node (ref "3.3V") (pin "1") (pinfunction "1_1") (pintype "passive"))
      (node (ref "R19") (pin "2") (pinfunction "2_2") (pintype "passive"))
      (node (ref "R20") (pin "1") (pinfunction "1_1") (pintype "passive"))
      (node (ref "R4") (pin "2") (pinfunction "2_2") (pintype "passive"))
      (node (ref "R5") (pin "2") (pinfunction "2_2") (pintype "passive"))
      (node (ref "SLOT1") (pin "20") (pinfunction "20_20") (pintype "passive"))
      (node (ref "SLOT1") (pin "28") (pinfunction "28_28") (pintype "passive"))
      (node (ref "SLOT1") (pin "32") (pinfunction "32_32") (pintype "passive"))
      (node (ref "SLOT2") (pin "20") (pinfunction "20_20") (pintype "passive"))
      (node (ref "SLOT2") (pin "28") (pinfunction "28_28") (pintype "passive"))
      (node (ref "SLOT2") (pin "32") (pinfunction "32_32") (pintype "passive"))
      (node (ref "XESS") (pin "54") (pinfunction "+3V3_54") (pintype "power_in"))
    )
    (net (code "3") (name "+5V") (class "Default")
      (node (ref "5V") (pin "2") (pinfunction "2_2") (pintype "passive"))
      (node (ref "C25") (pin "1") (pinfunction "1_1") (pintype "passive"))
      (node (ref "XESS") (pin "2") (pinfunction "+5V_2") (pintype "power_in"))
    )
    (net (code "4") (name "3S-LCLK") (class "Default")
      (node (ref "IC17") (pin "4") (pinfunction "A2_4") (pintype "input"))
      (node (ref "IC17") (pin "6") (pinfunction "A3_6") (pintype "input"))
      (node (ref "XESS") (pin "59") (pinfunction "M4_59") (pintype "bidirectional"))
    )
    (net (code "5") (name "3S-LSER") (class "Default")
      (node (ref "IC17") (pin "2") (pinfunction "A1_2") (pintype "input"))
      (node (ref "XESS") (pin "58") (pinfunction "P1_58") (pintype "bidirectional"))
    )
    (net (code "6") (name "3S-SCLK") (class "Default")
      (node (ref "IC17") (pin "15") (pinfunction "A3_15") (pintype "input"))
      (node (ref "XESS") (pin "12") (pinfunction "G12_12") (pintype "bidirectional"))
    )
    (net (code "7") (name "3S-SSER") (class "Default")
      (node (ref "D2") (pin "C") (pinfunction "C_C") (pintype "passive"))
      (node (ref "R11") (pin "2") (pinfunction "2_2") (pintype "passive"))
      (node (ref "XESS") (pin "14") (pinfunction "E16_14") (pintype "bidirectional"))
    )
    (net (code "8") (name "AC0") (class "Default")
      (node (ref "E40") (pin "7") (pinfunction "7_7") (pintype "passive"))
      (node (ref "R101") (pin "2") (pinfunction "2_2") (pintype "passive"))
    )
    (net (code "9") (name "AC1") (class "Default")
      (node (ref "E40") (pin "4") (pinfunction "4_4") (pintype "passive"))
      (node (ref "R106") (pin "2") (pinfunction "2_2") (pintype "passive"))
    )
    (net (code "10") (name "AC2") (class "Default")
      (node (ref "E40") (pin "21") (pinfunction "21_21") (pintype "passive"))
      (node (ref "R111") (pin "2") (pinfunction "2_2") (pintype "passive"))
    )
    (net (code "11") (name "AC3") (class "Default")
      (node (ref "E40") (pin "14") (pinfunction "14_14") (pintype "passive"))
      (node (ref "R116") (pin "2") (pinfunction "2_2") (pintype "passive"))
    )
    (net (code "12") (name "AC4") (class "Default")
      (node (ref "E40") (pin "31") (pinfunction "31_31") (pintype "passive"))
      (node (ref "R121") (pin "2") (pinfunction "2_2") (pintype "passive"))
    )
    (net (code "13") (name "AC5") (class "Default")
      (node (ref "E40") (pin "28") (pinfunction "28_28") (pintype "passive"))
      (node (ref "R126") (pin "2") (pinfunction "2_2") (pintype "passive"))
    )
    (net (code "14") (name "AC6") (class "Default")
      (node (ref "F40") (pin "7") (pinfunction "7_7") (pintype "passive"))
      (node (ref "R70") (pin "2") (pinfunction "2_2") (pintype "passive"))
    )
    (net (code "15") (name "AC7") (class "Default")
      (node (ref "F40") (pin "4") (pinfunction "4_4") (pintype "passive"))
      (node (ref "R75") (pin "2") (pinfunction "2_2") (pintype "passive"))
    )
    (net (code "16") (name "AC8") (class "Default")
      (node (ref "F40") (pin "21") (pinfunction "21_21") (pintype "passive"))
      (node (ref "R80") (pin "2") (pinfunction "2_2") (pintype "passive"))
    )
    (net (code "17") (name "AC9") (class "Default")
      (node (ref "F40") (pin "14") (pinfunction "14_14") (pintype "passive"))
      (node (ref "R85") (pin "2") (pinfunction "2_2") (pintype "passive"))
    )
    (net (code "18") (name "AC10") (class "Default")
      (node (ref "F40") (pin "31") (pinfunction "31_31") (pintype "passive"))
      (node (ref "R90") (pin "2") (pinfunction "2_2") (pintype "passive"))
    )
    (net (code "19") (name "AC11") (class "Default")
      (node (ref "F40") (pin "28") (pinfunction "28_28") (pintype "passive"))
      (node (ref "R95") (pin "2") (pinfunction "2_2") (pintype "passive"))
    )
    (net (code "20") (name "AND") (class "Default")
      (node (ref "D40") (pin "2") (pinfunction "2_2") (pintype "passive"))
      (node (ref "R54") (pin "2") (pinfunction "2_2") (pintype "passive"))
    )
    (net (code "21") (name "BREAK") (class "Default")
      (node (ref "D40") (pin "22") (pinfunction "22_22") (pintype "passive"))
      (node (ref "R57") (pin "2") (pinfunction "2_2") (pintype "passive"))
    )
    (net (code "22") (name "CA") (class "Default")
      (node (ref "D40") (pin "32") (pinfunction "32_32") (pintype "passive"))
      (node (ref "R63") (pin "2") (pinfunction "2_2") (pintype "passive"))
    )
    (net (code "23") (name "CF1") (class "Default")
      (node (ref "CONFIG") (pin "2") (pinfunction "2_2") (pintype "passive"))
      (node (ref "CONFIGSW") (pin "6") (pinfunction "6_6") (pintype "passive"))
      (node (ref "IC18") (pin "13") (pinfunction "C_13") (pintype "input"))
      (node (ref "R50") (pin "2") (pinfunction "2_2") (pintype "passive"))
    )
    (net (code "24") (name "CF2") (class "Default")
      (node (ref "CONFIG") (pin "4") (pinfunction "4_4") (pintype "passive"))
      (node (ref "CONFIGSW") (pin "5") (pinfunction "5_5") (pintype "passive"))
      (node (ref "IC18") (pin "14") (pinfunction "D_14") (pintype "input"))
      (node (ref "R6") (pin "2") (pinfunction "2_2") (pintype "passive"))
    )
    (net (code "25") (name "CF3") (class "Default")
      (node (ref "CONFIG") (pin "6") (pinfunction "6_6") (pintype "passive"))
      (node (ref "CONFIGSW") (pin "4") (pinfunction "4_4") (pintype "passive"))
      (node (ref "IC18") (pin "3") (pinfunction "E_3") (pintype "input"))
      (node (ref "R7") (pin "2") (pinfunction "2_2") (pintype "passive"))
    )
    (net (code "26") (name "CF4") (class "Default")
      (node (ref "CONFIG") (pin "8") (pinfunction "8_8") (pintype "passive"))
      (node (ref "CONFIGSW") (pin "3") (pinfunction "3_3") (pintype "passive"))
      (node (ref "IC18") (pin "4") (pinfunction "F_4") (pintype "input"))
      (node (ref "R8") (pin "2") (pinfunction "2_2") (pintype "passive"))
    )
    (net (code "27") (name "CF5") (class "Default")
      (node (ref "CONFIG") (pin "10") (pinfunction "10_10") (pintype "passive"))
      (node (ref "CONFIGSW") (pin "2") (pinfunction "2_2") (pintype "passive"))
      (node (ref "IC18") (pin "5") (pinfunction "G_5") (pintype "input"))
      (node (ref "R9") (pin "2") (pinfunction "2_2") (pintype "passive"))
    )
    (net (code "28") (name "CF6") (class "Default")
      (node (ref "CONFIG") (pin "12") (pinfunction "12_12") (pintype "passive"))
      (node (ref "CONFIGSW") (pin "1") (pinfunction "1_1") (pintype "passive"))
      (node (ref "IC18") (pin "6") (pinfunction "H_6") (pintype "input"))
      (node (ref "R10") (pin "2") (pinfunction "2_2") (pintype "passive"))
    )
    (net (code "29") (name "CLK") (class "Default")
      (node (ref "SLOT1") (pin "21") (pinfunction "21_21") (pintype "passive"))
      (node (ref "SLOT2") (pin "21") (pinfunction "21_21") (pintype "passive"))
      (node (ref "XESS") (pin "13") (pinfunction "F14_13") (pintype "bidirectional"))
    )
    (net (code "30") (name "CONT") (class "Default")
      (node (ref "B40") (pin "28") (pinfunction "28_28") (pintype "passive"))
      (node (ref "IC2") (pin "5") (pinfunction "G_5") (pintype "input"))
      (node (ref "R46") (pin "1") (pinfunction "1_1") (pintype "passive"))
    )
    (net (code "31") (name "DCA") (class "Default")
      (node (ref "D40") (pin "8") (pinfunction "8_8") (pintype "passive"))
      (node (ref "R51") (pin "2") (pinfunction "2_2") (pintype "passive"))
    )
    (net (code "32") (name "DEFER") (class "Default")
      (node (ref "D40") (pin "26") (pinfunction "26_26") (pintype "passive"))
      (node (ref "R66") (pin "2") (pinfunction "2_2") (pintype "passive"))
    )
    (net (code "33") (name "DEP") (class "Default")
      (node (ref "B40") (pin "20") (pinfunction "20_20") (pintype "passive"))
      (node (ref "IC2") (pin "3") (pinfunction "E_3") (pintype "input"))
      (node (ref "R44") (pin "1") (pinfunction "1_1") (pintype "passive"))
    )
    (net (code "34") (name "DF0") (class "Default")
      (node (ref "C40") (pin "1") (pinfunction "1_1") (pintype "passive"))
      (node (ref "R128") (pin "2") (pinfunction "2_2") (pintype "passive"))
    )
    (net (code "35") (name "DF1") (class "Default")
      (node (ref "C40") (pin "10") (pinfunction "10_10") (pintype "passive"))
      (node (ref "R130") (pin "2") (pinfunction "2_2") (pintype "passive"))
    )
    (net (code "36") (name "DF2") (class "Default")
      (node (ref "C40") (pin "11") (pinfunction "11_11") (pintype "passive"))
      (node (ref "R132") (pin "2") (pinfunction "2_2") (pintype "passive"))
    )
    (net (code "37") (name "EXAM") (class "Default")
      (node (ref "B40") (pin "26") (pinfunction "26_26") (pintype "passive"))
      (node (ref "IC2") (pin "4") (pinfunction "F_4") (pintype "input"))
      (node (ref "R45") (pin "1") (pinfunction "1_1") (pintype "passive"))
    )
    (net (code "38") (name "EXECUTE") (class "Default")
      (node (ref "D40") (pin "28") (pinfunction "28_28") (pintype "passive"))
      (node (ref "R65") (pin "2") (pinfunction "2_2") (pintype "passive"))
    )
    (net (code "39") (name "FETCH") (class "Default")
      (node (ref "D40") (pin "24") (pinfunction "24_24") (pintype "passive"))
      (node (ref "R56") (pin "2") (pinfunction "2_2") (pintype "passive"))
    )
    (net (code "40") (name "GND") (class "Default")
      (node (ref "A40") (pin "4") (pinfunction "4_4") (pintype "passive"))
      (node (ref "B40") (pin "4") (pinfunction "4_4") (pintype "passive"))
      (node (ref "C10") (pin "2") (pinfunction "2_2") (pintype "passive"))
      (node (ref "C11") (pin "2") (pinfunction "2_2") (pintype "passive"))
      (node (ref "C12") (pin "2") (pinfunction "2_2") (pintype "passive"))
      (node (ref "C13") (pin "2") (pinfunction "2_2") (pintype "passive"))
      (node (ref "C14") (pin "2") (pinfunction "2_2") (pintype "passive"))
      (node (ref "C15") (pin "2") (pinfunction "2_2") (pintype "passive"))
      (node (ref "C16") (pin "2") (pinfunction "2_2") (pintype "passive"))
      (node (ref "C17") (pin "2") (pinfunction "2_2") (pintype "passive"))
      (node (ref "C18") (pin "2") (pinfunction "2_2") (pintype "passive"))
      (node (ref "C19") (pin "2") (pinfunction "2_2") (pintype "passive"))
      (node (ref "C20") (pin "2") (pinfunction "2_2") (pintype "passive"))
      (node (ref "C21") (pin "2") (pinfunction "2_2") (pintype "passive"))
      (node (ref "C22") (pin "2") (pinfunction "2_2") (pintype "passive"))
      (node (ref "C23") (pin "2") (pinfunction "2_2") (pintype "passive"))
      (node (ref "C24") (pin "2") (pinfunction "2_2") (pintype "passive"))
      (node (ref "C25") (pin "2") (pinfunction "2_2") (pintype "passive"))
      (node (ref "C4") (pin "2") (pinfunction "2_2") (pintype "passive"))
      (node (ref "C40") (pin "17") (pinfunction "17_17") (pintype "passive"))
      (node (ref "C40") (pin "18") (pinfunction "18_18") (pintype "passive"))
      (node (ref "C40") (pin "19") (pinfunction "19_19") (pintype "passive"))
      (node (ref "C40") (pin "20") (pinfunction "20_20") (pintype "passive"))
      (node (ref "C5") (pin "2") (pinfunction "2_2") (pintype "passive"))
      (node (ref "C6") (pin "2") (pinfunction "2_2") (pintype "passive"))
      (node (ref "C7") (pin "2") (pinfunction "2_2") (pintype "passive"))
      (node (ref "C8") (pin "2") (pinfunction "2_2") (pintype "passive"))
      (node (ref "C9") (pin "2") (pinfunction "2_2") (pintype "passive"))
      (node (ref "CONFIG") (pin "1") (pinfunction "1_1") (pintype "passive"))
      (node (ref "CONFIG") (pin "11") (pinfunction "11_11") (pintype "passive"))
      (node (ref "CONFIG") (pin "3") (pinfunction "3_3") (pintype "passive"))
      (node (ref "CONFIG") (pin "5") (pinfunction "5_5") (pintype "passive"))
      (node (ref "CONFIG") (pin "7") (pinfunction "7_7") (pintype "passive"))
      (node (ref "CONFIG") (pin "9") (pinfunction "9_9") (pintype "passive"))
      (node (ref "CONFIGSW") (pin "10") (pinfunction "10_10") (pintype "passive"))
      (node (ref "CONFIGSW") (pin "11") (pinfunction "11_11") (pintype "passive"))
      (node (ref "CONFIGSW") (pin "12") (pinfunction "12_12") (pintype "passive"))
      (node (ref "CONFIGSW") (pin "13") (pinfunction "13_13") (pintype "passive"))
      (node (ref "CONFIGSW") (pin "14") (pinfunction "14_14") (pintype "passive"))
      (node (ref "CONFIGSW") (pin "15") (pinfunction "15_15") (pintype "passive"))
      (node (ref "CONFIGSW") (pin "16") (pinfunction "16_16") (pintype "passive"))
      (node (ref "CONFIGSW") (pin "17") (pinfunction "17_17") (pintype "passive"))
      (node (ref "CONFIGSW") (pin "18") (pinfunction "18_18") (pintype "passive"))
      (node (ref "D1") (pin "A") (pinfunction "A_A") (pintype "passive"))
      (node (ref "D2") (pin "A") (pinfunction "A_A") (pintype "passive"))
      (node (ref "D40") (pin "17") (pinfunction "17_17") (pintype "passive"))
      (node (ref "D40") (pin "18") (pinfunction "18_18") (pintype "passive"))
      (node (ref "D40") (pin "19") (pinfunction "19_19") (pintype "passive"))
      (node (ref "D40") (pin "20") (pinfunction "20_20") (pintype "passive"))
      (node (ref "E40") (pin "17") (pinfunction "17_17") (pintype "passive"))
      (node (ref "E40") (pin "18") (pinfunction "18_18") (pintype "passive"))
      (node (ref "E40") (pin "19") (pinfunction "19_19") (pintype "passive"))
      (node (ref "E40") (pin "20") (pinfunction "20_20") (pintype "passive"))
      (node (ref "EXTRESET") (pin "3") (pinfunction "P_3") (pintype "passive"))
      (node (ref "EXTRESET") (pin "4") (pinfunction "P1_4") (pintype "passive"))
      (node (ref "F40") (pin "17") (pinfunction "17_17") (pintype "passive"))
      (node (ref "F40") (pin "18") (pinfunction "18_18") (pintype "passive"))
      (node (ref "F40") (pin "19") (pinfunction "19_19") (pintype "passive"))
      (node (ref "F40") (pin "20") (pinfunction "20_20") (pintype "passive"))
      (node (ref "GND1") (pin "1") (pinfunction "1_1") (pintype "passive"))
      (node (ref "GND2") (pin "1") (pinfunction "1_1") (pintype "passive"))
      (node (ref "GND3") (pin "1") (pinfunction "1_1") (pintype "passive"))
      (node (ref "GND4") (pin "1") (pinfunction "1_1") (pintype "passive"))
      (node (ref "IC1") (pin "13") (pinfunction "G_13") (pintype "input"))
      (node (ref "IC10") (pin "13") (pinfunction "G_13") (pintype "input"))
      (node (ref "IC11") (pin "13") (pinfunction "G_13") (pintype "input"))
      (node (ref "IC12") (pin "13") (pinfunction "G_13") (pintype "input"))
      (node (ref "IC13") (pin "13") (pinfunction "G_13") (pintype "input"))
      (node (ref "IC14") (pin "10") (pinfunction "SER_10") (pintype "input"))
      (node (ref "IC14") (pin "15") (pinfunction "INH_15") (pintype "input"))
      (node (ref "IC15") (pin "15") (pinfunction "INH_15") (pintype "input"))
      (node (ref "IC16") (pin "13") (pinfunction "G_13") (pintype "input"))
      (node (ref "IC17") (pin "1") (pinfunction "G_1") (pintype "input"))
      (node (ref "IC17") (pin "19") (pinfunction "G_19") (pintype "input"))
      (node (ref "IC18") (pin "15") (pinfunction "INH_15") (pintype "input"))
      (node (ref "IC2") (pin "15") (pinfunction "INH_15") (pintype "input"))
      (node (ref "IC4") (pin "13") (pinfunction "G_13") (pintype "input"))
      (node (ref "IC5") (pin "13") (pinfunction "G_13") (pintype "input"))
      (node (ref "IC6") (pin "13") (pinfunction "G_13") (pintype "input"))
      (node (ref "IC7") (pin "13") (pinfunction "G_13") (pintype "input"))
      (node (ref "IC8") (pin "13") (pinfunction "G_13") (pintype "input"))
      (node (ref "IC9") (pin "13") (pinfunction "G_13") (pintype "input"))
      (node (ref "IDE") (pin "19") (pinfunction "19_19") (pintype "passive"))
      (node (ref "IDE") (pin "2") (pinfunction "2_2") (pintype "passive"))
      (node (ref "IDE") (pin "22") (pinfunction "22_22") (pintype "passive"))
      (node (ref "IDE") (pin "24") (pinfunction "24_24") (pintype "passive"))
      (node (ref "IDE") (pin "26") (pinfunction "26_26") (pintype "passive"))
      (node (ref "IDE") (pin "28") (pinfunction "28_28") (pintype "passive"))
      (node (ref "IDE") (pin "30") (pinfunction "30_30") (pintype "passive"))
      (node (ref "IDE") (pin "40") (pinfunction "40_40") (pintype "passive"))
      (node (ref "J1") (pin "2") (pinfunction "2_2") (pintype "passive"))
      (node (ref "J1") (pin "3") (pinfunction "3_3") (pintype "passive"))
      (node (ref "J3") (pin "2") (pinfunction "2_2") (pintype "passive"))
      (node (ref "J4") (pin "11") (pinfunction "CMN_11") (pintype "input"))
      (node (ref "LOCKSW") (pin "1") (pinfunction "1_1") (pintype "passive"))
      (node (ref "R17") (pin "1") (pinfunction "1_1") (pintype "passive"))
      (node (ref "R18") (pin "1") (pinfunction "1_1") (pintype "passive"))
      (node (ref "RS-232") (pin "3") (pinfunction "3_3") (pintype "passive"))
      (node (ref "SLOT1") (pin "19") (pinfunction "19_19") (pintype "passive"))
      (node (ref "SLOT1") (pin "2") (pinfunction "2_2") (pintype "passive"))
      (node (ref "SLOT1") (pin "22") (pinfunction "22_22") (pintype "passive"))
      (node (ref "SLOT1") (pin "24") (pinfunction "24_24") (pintype "passive"))
      (node (ref "SLOT1") (pin "26") (pinfunction "26_26") (pintype "passive"))
      (node (ref "SLOT1") (pin "30") (pinfunction "30_30") (pintype "passive"))
      (node (ref "SLOT1") (pin "40") (pinfunction "40_40") (pintype "passive"))
      (node (ref "SLOT2") (pin "19") (pinfunction "19_19") (pintype "passive"))
      (node (ref "SLOT2") (pin "2") (pinfunction "2_2") (pintype "passive"))
      (node (ref "SLOT2") (pin "22") (pinfunction "22_22") (pintype "passive"))
      (node (ref "SLOT2") (pin "24") (pinfunction "24_24") (pintype "passive"))
      (node (ref "SLOT2") (pin "26") (pinfunction "26_26") (pintype "passive"))
      (node (ref "SLOT2") (pin "30") (pinfunction "30_30") (pintype "passive"))
      (node (ref "SLOT2") (pin "40") (pinfunction "40_40") (pintype "passive"))
      (node (ref "V-") (pin "1") (pinfunction "1_1") (pintype "passive"))
      (node (ref "X1") (pin "5") (pinfunction "F_5") (pintype "passive"))
      (node (ref "X1") (pin "G1") (pinfunction "G1_G1") (pintype "passive"))
      (node (ref "X1") (pin "G2") (pinfunction "G2_G2") (pintype "passive"))
      (node (ref "XESS") (pin "52") (pinfunction "GND_52") (pintype "power_in"))
    )
    (net (code "41") (name "I2C-SCL") (class "Default")
      (node (ref "SLOT1") (pin "27") (pinfunction "27_27") (pintype "passive"))
      (node (ref "SLOT2") (pin "27") (pinfunction "27_27") (pintype "passive"))
      (node (ref "XESS") (pin "23") (pinfunction "F5_23") (pintype "bidirectional"))
    )
    (net (code "42") (name "I2C-SDA") (class "Default")
      (node (ref "SLOT1") (pin "29") (pinfunction "29_29") (pintype "passive"))
      (node (ref "SLOT2") (pin "29") (pinfunction "29_29") (pintype "passive"))
      (node (ref "XESS") (pin "24") (pinfunction "D2_24") (pintype "bidirectional"))
    )
    (net (code "43") (name "IDE-CS0#") (class "Default")
      (node (ref "IDE") (pin "37") (pinfunction "37_37") (pintype "passive"))
      (node (ref "XESS") (pin "7") (pinfunction "G15_7") (pintype "bidirectional"))
    )
    (net (code "44") (name "IDE-CS1#") (class "Default")
      (node (ref "IDE") (pin "38") (pinfunction "38_38") (pintype "passive"))
      (node (ref "XESS") (pin "8") (pinfunction "G14_8") (pintype "bidirectional"))
    )
    (net (code "45") (name "IDE-DMACK#") (class "Default")
      (node (ref "IDE") (pin "29") (pinfunction "29_29") (pintype "passive"))
      (node (ref "XESS") (pin "43") (pinfunction "K1_43") (pintype "bidirectional"))
    )
    (net (code "46") (name "IDE-DMARQ") (class "Default")
      (node (ref "R12") (pin "1") (pinfunction "1_1") (pintype "passive"))
      (node (ref "R17") (pin "2") (pinfunction "2_2") (pintype "passive"))
      (node (ref "XESS") (pin "49") (pinfunction "L4_49") (pintype "bidirectional"))
    )
    (net (code "47") (name "IDE-IORDY") (class "Default")
      (node (ref "R15") (pin "1") (pinfunction "1_1") (pintype "passive"))
      (node (ref "R19") (pin "1") (pinfunction "1_1") (pintype "passive"))
      (node (ref "XESS") (pin "44") (pinfunction "L2_44") (pintype "bidirectional"))
    )
    (net (code "48") (name "IDE-IRQ") (class "Default")
      (node (ref "R16") (pin "1") (pinfunction "1_1") (pintype "passive"))
      (node (ref "R18") (pin "2") (pinfunction "2_2") (pintype "passive"))
      (node (ref "XESS") (pin "3") (pinfunction "H15_3") (pintype "bidirectional"))
    )
    (net (code "49") (name "IF0") (class "Default")
      (node (ref "C40") (pin "24") (pinfunction "24_24") (pintype "passive"))
      (node (ref "R134") (pin "2") (pinfunction "2_2") (pintype "passive"))
    )
    (net (code "50") (name "IF1") (class "Default")
      (node (ref "C40") (pin "25") (pinfunction "25_25") (pintype "passive"))
      (node (ref "R136") (pin "2") (pinfunction "2_2") (pintype "passive"))
    )
    (net (code "51") (name "IF2") (class "Default")
      (node (ref "C40") (pin "34") (pinfunction "34_34") (pintype "passive"))
      (node (ref "R138") (pin "2") (pinfunction "2_2") (pintype "passive"))
    )
    (net (code "52") (name "ION") (class "Default")
      (node (ref "D40") (pin "34") (pinfunction "34_34") (pintype "passive"))
      (node (ref "R62") (pin "2") (pinfunction "2_2") (pintype "passive"))
    )
    (net (code "53") (name "IOT") (class "Default")
      (node (ref "D40") (pin "23") (pinfunction "23_23") (pintype "passive"))
      (node (ref "R55") (pin "2") (pinfunction "2_2") (pintype "passive"))
    )
    (net (code "54") (name "ISZ") (class "Default")
      (node (ref "D40") (pin "6") (pinfunction "6_6") (pintype "passive"))
      (node (ref "R52") (pin "2") (pinfunction "2_2") (pintype "passive"))
    )
    (net (code "55") (name "JMP") (class "Default")
      (node (ref "D40") (pin "12") (pinfunction "12_12") (pintype "passive"))
      (node (ref "R59") (pin "2") (pinfunction "2_2") (pintype "passive"))
    )
    (net (code "56") (name "JMS") (class "Default")
      (node (ref "D40") (pin "10") (pinfunction "10_10") (pintype "passive"))
      (node (ref "R97") (pin "2") (pinfunction "2_2") (pintype "passive"))
    )
    (net (code "57") (name "LA") (class "Default")
      (node (ref "B40") (pin "18") (pinfunction "18_18") (pintype "passive"))
      (node (ref "IC2") (pin "14") (pinfunction "D_14") (pintype "input"))
      (node (ref "R43") (pin "1") (pinfunction "1_1") (pintype "passive"))
    )
    (net (code "58") (name "LCLK") (class "Default")
      (node (ref "IC1") (pin "11") (pinfunction "SCK_11") (pintype "input"))
      (node (ref "IC10") (pin "11") (pinfunction "SCK_11") (pintype "input"))
      (node (ref "IC11") (pin "11") (pinfunction "SCK_11") (pintype "input"))
      (node (ref "IC12") (pin "11") (pinfunction "SCK_11") (pintype "input"))
      (node (ref "IC13") (pin "11") (pinfunction "SCK_11") (pintype "input"))
      (node (ref "IC16") (pin "11") (pinfunction "SCK_11") (pintype "input"))
      (node (ref "IC17") (pin "14") (pinfunction "Y3_14") (pintype "tri_state"))
      (node (ref "IC17") (pin "16") (pinfunction "Y2_16") (pintype "tri_state"))
      (node (ref "IC19") (pin "1") (pinfunction "I0_1") (pintype "input"))
      (node (ref "IC19") (pin "2") (pinfunction "I1_2") (pintype "input"))
      (node (ref "IC4") (pin "11") (pinfunction "SCK_11") (pintype "input"))
      (node (ref "IC5") (pin "11") (pinfunction "SCK_11") (pintype "input"))
      (node (ref "IC6") (pin "11") (pinfunction "SCK_11") (pintype "input"))
      (node (ref "IC7") (pin "11") (pinfunction "SCK_11") (pintype "input"))
      (node (ref "IC8") (pin "11") (pinfunction "SCK_11") (pintype "input"))
      (node (ref "IC9") (pin "11") (pinfunction "SCK_11") (pintype "input"))
      (node (ref "SV1") (pin "3") (pinfunction "3_3") (pintype "passive"))
      (node (ref "SV2") (pin "3") (pinfunction "3_3") (pintype "passive"))
    )
    (net (code "59") (name "LEFT") (class "Default")
      (node (ref "IC8") (pin "9") (pinfunction "QH*_9") (pintype "tri_state"))
      (node (ref "IC9") (pin "14") (pinfunction "SER_14") (pintype "input"))
      (node (ref "SV1") (pin "1") (pinfunction "1_1") (pintype "passive"))
      (node (ref "SV2") (pin "1") (pinfunction "1_1") (pintype "passive"))
    )
    (net (code "60") (name "LINK") (class "Default")
      (node (ref "C40") (pin "28") (pinfunction "28_28") (pintype "passive"))
      (node (ref "R139") (pin "2") (pinfunction "2_2") (pintype "passive"))
    )
    (net (code "61") (name "LSER") (class "Default")
      (node (ref "IC1") (pin "14") (pinfunction "SER_14") (pintype "input"))
      (node (ref "IC17") (pin "18") (pinfunction "Y1_18") (pintype "tri_state"))
      (node (ref "SV1") (pin "9") (pinfunction "9_9") (pintype "passive"))
      (node (ref "SV2") (pin "9") (pinfunction "9_9") (pintype "passive"))
    )
    (net (code "62") (name "MA0") (class "Default")
      (node (ref "E40") (pin "3") (pinfunction "3_3") (pintype "passive"))
      (node (ref "R99") (pin "2") (pinfunction "2_2") (pintype "passive"))
    )
    (net (code "63") (name "MA1") (class "Default")
      (node (ref "E40") (pin "8") (pinfunction "8_8") (pintype "passive"))
      (node (ref "R104") (pin "2") (pinfunction "2_2") (pintype "passive"))
    )
    (net (code "64") (name "MA2") (class "Default")
      (node (ref "E40") (pin "13") (pinfunction "13_13") (pintype "passive"))
      (node (ref "R109") (pin "2") (pinfunction "2_2") (pintype "passive"))
    )
    (net (code "65") (name "MA3") (class "Default")
      (node (ref "E40") (pin "22") (pinfunction "22_22") (pintype "passive"))
      (node (ref "R114") (pin "2") (pinfunction "2_2") (pintype "passive"))
    )
    (net (code "66") (name "MA4") (class "Default")
      (node (ref "E40") (pin "27") (pinfunction "27_27") (pintype "passive"))
      (node (ref "R119") (pin "2") (pinfunction "2_2") (pintype "passive"))
    )
    (net (code "67") (name "MA5") (class "Default")
      (node (ref "E40") (pin "32") (pinfunction "32_32") (pintype "passive"))
      (node (ref "R124") (pin "2") (pinfunction "2_2") (pintype "passive"))
    )
    (net (code "68") (name "MA6") (class "Default")
      (node (ref "F40") (pin "3") (pinfunction "3_3") (pintype "passive"))
      (node (ref "R68") (pin "2") (pinfunction "2_2") (pintype "passive"))
    )
    (net (code "69") (name "MA7") (class "Default")
      (node (ref "F40") (pin "8") (pinfunction "8_8") (pintype "passive"))
      (node (ref "R73") (pin "2") (pinfunction "2_2") (pintype "passive"))
    )
    (net (code "70") (name "MA8") (class "Default")
      (node (ref "F40") (pin "13") (pinfunction "13_13") (pintype "passive"))
      (node (ref "R78") (pin "2") (pinfunction "2_2") (pintype "passive"))
    )
    (net (code "71") (name "MA9") (class "Default")
      (node (ref "F40") (pin "22") (pinfunction "22_22") (pintype "passive"))
      (node (ref "R83") (pin "2") (pinfunction "2_2") (pintype "passive"))
    )
    (net (code "72") (name "MA10") (class "Default")
      (node (ref "F40") (pin "27") (pinfunction "27_27") (pintype "passive"))
      (node (ref "R88") (pin "2") (pinfunction "2_2") (pintype "passive"))
    )
    (net (code "73") (name "MA11") (class "Default")
      (node (ref "F40") (pin "32") (pinfunction "32_32") (pintype "passive"))
      (node (ref "R93") (pin "2") (pinfunction "2_2") (pintype "passive"))
    )
    (net (code "74") (name "MASTER-RESET#") (class "Default")
      (node (ref "IC17") (pin "3") (pinfunction "Y4_3") (pintype "tri_state"))
      (node (ref "IDE") (pin "1") (pinfunction "1_1") (pintype "passive"))
      (node (ref "SLOT1") (pin "1") (pinfunction "1_1") (pintype "passive"))
      (node (ref "SLOT2") (pin "1") (pinfunction "1_1") (pintype "passive"))
    )
    (net (code "75") (name "MB0") (class "Default")
      (node (ref "E40") (pin "5") (pinfunction "5_5") (pintype "passive"))
      (node (ref "R100") (pin "2") (pinfunction "2_2") (pintype "passive"))
    )
    (net (code "76") (name "MB1") (class "Default")
      (node (ref "E40") (pin "6") (pinfunction "6_6") (pintype "passive"))
      (node (ref "R105") (pin "2") (pinfunction "2_2") (pintype "passive"))
    )
    (net (code "77") (name "MB2") (class "Default")
      (node (ref "E40") (pin "15") (pinfunction "15_15") (pintype "passive"))
      (node (ref "R110") (pin "2") (pinfunction "2_2") (pintype "passive"))
    )
    (net (code "78") (name "MB3") (class "Default")
      (node (ref "E40") (pin "16") (pinfunction "16_16") (pintype "passive"))
      (node (ref "R115") (pin "2") (pinfunction "2_2") (pintype "passive"))
    )
    (net (code "79") (name "MB4") (class "Default")
      (node (ref "E40") (pin "29") (pinfunction "29_29") (pintype "passive"))
      (node (ref "R120") (pin "2") (pinfunction "2_2") (pintype "passive"))
    )
    (net (code "80") (name "MB5") (class "Default")
      (node (ref "E40") (pin "30") (pinfunction "30_30") (pintype "passive"))
      (node (ref "R125") (pin "2") (pinfunction "2_2") (pintype "passive"))
    )
    (net (code "81") (name "MB6") (class "Default")
      (node (ref "F40") (pin "5") (pinfunction "5_5") (pintype "passive"))
      (node (ref "R69") (pin "2") (pinfunction "2_2") (pintype "passive"))
    )
    (net (code "82") (name "MB7") (class "Default")
      (node (ref "F40") (pin "6") (pinfunction "6_6") (pintype "passive"))
      (node (ref "R74") (pin "2") (pinfunction "2_2") (pintype "passive"))
    )
    (net (code "83") (name "MB8") (class "Default")
      (node (ref "F40") (pin "15") (pinfunction "15_15") (pintype "passive"))
      (node (ref "R79") (pin "2") (pinfunction "2_2") (pintype "passive"))
    )
    (net (code "84") (name "MB9") (class "Default")
      (node (ref "F40") (pin "16") (pinfunction "16_16") (pintype "passive"))
      (node (ref "R84") (pin "2") (pinfunction "2_2") (pintype "passive"))
    )
    (net (code "85") (name "MB10") (class "Default")
      (node (ref "F40") (pin "29") (pinfunction "29_29") (pintype "passive"))
      (node (ref "R89") (pin "2") (pinfunction "2_2") (pintype "passive"))
    )
    (net (code "86") (name "MB11") (class "Default")
      (node (ref "F40") (pin "30") (pinfunction "30_30") (pintype "passive"))
      (node (ref "R94") (pin "2") (pinfunction "2_2") (pintype "passive"))
    )
    (net (code "87") (name "MQ0") (class "Default")
      (node (ref "E40") (pin "9") (pinfunction "9_9") (pintype "passive"))
      (node (ref "R102") (pin "2") (pinfunction "2_2") (pintype "passive"))
    )
    (net (code "88") (name "MQ1") (class "Default")
      (node (ref "E40") (pin "2") (pinfunction "2_2") (pintype "passive"))
      (node (ref "R107") (pin "2") (pinfunction "2_2") (pintype "passive"))
    )
    (net (code "89") (name "MQ2") (class "Default")
      (node (ref "E40") (pin "23") (pinfunction "23_23") (pintype "passive"))
      (node (ref "R112") (pin "2") (pinfunction "2_2") (pintype "passive"))
    )
    (net (code "90") (name "MQ3") (class "Default")
      (node (ref "E40") (pin "12") (pinfunction "12_12") (pintype "passive"))
      (node (ref "R117") (pin "2") (pinfunction "2_2") (pintype "passive"))
    )
    (net (code "91") (name "MQ4") (class "Default")
      (node (ref "E40") (pin "33") (pinfunction "33_33") (pintype "passive"))
      (node (ref "R122") (pin "2") (pinfunction "2_2") (pintype "passive"))
    )
    (net (code "92") (name "MQ5") (class "Default")
      (node (ref "E40") (pin "26") (pinfunction "26_26") (pintype "passive"))
      (node (ref "R127") (pin "2") (pinfunction "2_2") (pintype "passive"))
    )
    (net (code "93") (name "MQ6") (class "Default")
      (node (ref "F40") (pin "9") (pinfunction "9_9") (pintype "passive"))
      (node (ref "R71") (pin "2") (pinfunction "2_2") (pintype "passive"))
    )
    (net (code "94") (name "MQ7") (class "Default")
      (node (ref "F40") (pin "2") (pinfunction "2_2") (pintype "passive"))
      (node (ref "R76") (pin "2") (pinfunction "2_2") (pintype "passive"))
    )
    (net (code "95") (name "MQ8") (class "Default")
      (node (ref "F40") (pin "23") (pinfunction "23_23") (pintype "passive"))
      (node (ref "R81") (pin "2") (pinfunction "2_2") (pintype "passive"))
    )
    (net (code "96") (name "MQ9") (class "Default")
      (node (ref "F40") (pin "12") (pinfunction "12_12") (pintype "passive"))
      (node (ref "R86") (pin "2") (pinfunction "2_2") (pintype "passive"))
    )
    (net (code "97") (name "MQ10") (class "Default")
      (node (ref "F40") (pin "33") (pinfunction "33_33") (pintype "passive"))
      (node (ref "R91") (pin "2") (pinfunction "2_2") (pintype "passive"))
    )
    (net (code "98") (name "MQ11") (class "Default")
      (node (ref "F40") (pin "26") (pinfunction "26_26") (pintype "passive"))
      (node (ref "R96") (pin "2") (pinfunction "2_2") (pintype "passive"))
    )
    (net (code "99") (name "Net-(+12V-Pad1)") (class "Default")
      (node (ref "+12V") (pin "1") (pinfunction "1_1") (pintype "passive"))
      (node (ref "J1") (pin "1") (pinfunction "1_1") (pintype "passive"))
    )
    (net (code "100") (name "Net-(EXTRESET-S)") (class "Default")
      (node (ref "C5") (pin "1") (pinfunction "1_1") (pintype "passive"))
      (node (ref "EXTRESET") (pin "1") (pinfunction "S_1") (pintype "passive"))
      (node (ref "EXTRESET") (pin "2") (pinfunction "S1_2") (pintype "passive"))
      (node (ref "IC17") (pin "17") (pinfunction "A4_17") (pintype "input"))
      (node (ref "R20") (pin "2") (pinfunction "2_2") (pintype "passive"))
      (node (ref "R23") (pin "2") (pinfunction "2_2") (pintype "passive"))
    )
    (net (code "101") (name "Net-(IC1A-QA)") (class "Default")
      (node (ref "IC1") (pin "15") (pinfunction "QA_15") (pintype "tri_state"))
      (node (ref "R128") (pin "1") (pinfunction "1_1") (pintype "passive"))
    )
    (net (code "102") (name "Net-(IC1A-QB)") (class "Default")
      (node (ref "IC1") (pin "1") (pinfunction "QB_1") (pintype "tri_state"))
      (node (ref "R129") (pin "1") (pinfunction "1_1") (pintype "passive"))
    )
    (net (code "103") (name "Net-(IC1A-QC)") (class "Default")
      (node (ref "IC1") (pin "2") (pinfunction "QC_2") (pintype "tri_state"))
      (node (ref "R130") (pin "1") (pinfunction "1_1") (pintype "passive"))
    )
    (net (code "104") (name "Net-(IC1A-QD)") (class "Default")
      (node (ref "IC1") (pin "3") (pinfunction "QD_3") (pintype "tri_state"))
      (node (ref "R131") (pin "1") (pinfunction "1_1") (pintype "passive"))
    )
    (net (code "105") (name "Net-(IC1A-QE)") (class "Default")
      (node (ref "IC1") (pin "4") (pinfunction "QE_4") (pintype "tri_state"))
      (node (ref "R132") (pin "1") (pinfunction "1_1") (pintype "passive"))
    )
    (net (code "106") (name "Net-(IC1A-QF)") (class "Default")
      (node (ref "IC1") (pin "5") (pinfunction "QF_5") (pintype "tri_state"))
      (node (ref "R133") (pin "1") (pinfunction "1_1") (pintype "passive"))
    )
    (net (code "107") (name "Net-(IC1A-QG)") (class "Default")
      (node (ref "IC1") (pin "6") (pinfunction "QG_6") (pintype "tri_state"))
      (node (ref "R134") (pin "1") (pinfunction "1_1") (pintype "passive"))
    )
    (net (code "108") (name "Net-(IC1A-QH)") (class "Default")
      (node (ref "IC1") (pin "7") (pinfunction "QH_7") (pintype "tri_state"))
      (node (ref "R135") (pin "1") (pinfunction "1_1") (pintype "passive"))
    )
    (net (code "109") (name "Net-(IC1A-QH*)") (class "Default")
      (node (ref "IC1") (pin "9") (pinfunction "QH*_9") (pintype "tri_state"))
      (node (ref "IC4") (pin "14") (pinfunction "SER_14") (pintype "input"))
    )
    (net (code "110") (name "Net-(IC3A-C1+)") (class "Default")
      (node (ref "C2") (pin "1") (pinfunction "1_1") (pintype "passive"))
      (node (ref "IC3") (pin "1") (pinfunction "C1+_1") (pintype "bidirectional"))
    )
    (net (code "111") (name "Net-(IC3A-C1-)") (class "Default")
      (node (ref "C2") (pin "2") (pinfunction "2_2") (pintype "passive"))
      (node (ref "IC3") (pin "3") (pinfunction "C1-_3") (pintype "bidirectional"))
    )
    (net (code "112") (name "Net-(IC3A-C2+)") (class "Default")
      (node (ref "C3") (pin "1") (pinfunction "1_1") (pintype "passive"))
      (node (ref "IC3") (pin "4") (pinfunction "C2+_4") (pintype "bidirectional"))
    )
    (net (code "113") (name "Net-(IC3A-C2-)") (class "Default")
      (node (ref "C3") (pin "2") (pinfunction "2_2") (pintype "passive"))
      (node (ref "IC3") (pin "5") (pinfunction "C2-_5") (pintype "bidirectional"))
    )
    (net (code "114") (name "Net-(IC3A-R2OUT)") (class "Default")
      (node (ref "IC3") (pin "9") (pinfunction "R2OUT_9") (pintype "output"))
      (node (ref "R2") (pin "2") (pinfunction "2_2") (pintype "passive"))
    )
    (net (code "115") (name "Net-(IC3A-T1IN)") (class "Default")
      (node (ref "IC3") (pin "11") (pinfunction "T1IN_11") (pintype "input"))
      (node (ref "R1") (pin "2") (pinfunction "2_2") (pintype "passive"))
    )
    (net (code "116") (name "Net-(IC3A-T2IN)") (class "Default")
      (node (ref "IC3") (pin "10") (pinfunction "T2IN_10") (pintype "input"))
      (node (ref "R3") (pin "2") (pinfunction "2_2") (pintype "passive"))
    )
    (net (code "117") (name "Net-(IC3A-V+)") (class "Default")
      (node (ref "C1") (pin "2") (pinfunction "2_2") (pintype "passive"))
      (node (ref "IC3") (pin "2") (pinfunction "V+_2") (pintype "bidirectional"))
    )
    (net (code "118") (name "Net-(IC3A-V-)") (class "Default")
      (node (ref "C4") (pin "1") (pinfunction "1_1") (pintype "passive"))
      (node (ref "IC3") (pin "6") (pinfunction "V-_6") (pintype "bidirectional"))
    )
    (net (code "119") (name "Net-(IC4A-QA)") (class "Default")
      (node (ref "IC4") (pin "15") (pinfunction "QA_15") (pintype "tri_state"))
      (node (ref "R136") (pin "1") (pinfunction "1_1") (pintype "passive"))
    )
    (net (code "120") (name "Net-(IC4A-QB)") (class "Default")
      (node (ref "IC4") (pin "1") (pinfunction "QB_1") (pintype "tri_state"))
      (node (ref "R137") (pin "1") (pinfunction "1_1") (pintype "passive"))
    )
    (net (code "121") (name "Net-(IC4A-QC)") (class "Default")
      (node (ref "IC4") (pin "2") (pinfunction "QC_2") (pintype "tri_state"))
      (node (ref "R138") (pin "1") (pinfunction "1_1") (pintype "passive"))
    )
    (net (code "122") (name "Net-(IC4A-QD)") (class "Default")
      (node (ref "IC4") (pin "3") (pinfunction "QD_3") (pintype "tri_state"))
      (node (ref "R139") (pin "1") (pinfunction "1_1") (pintype "passive"))
    )
    (net (code "123") (name "Net-(IC4A-QH*)") (class "Default")
      (node (ref "IC4") (pin "9") (pinfunction "QH*_9") (pintype "tri_state"))
      (node (ref "IC5") (pin "14") (pinfunction "SER_14") (pintype "input"))
    )
    (net (code "124") (name "Net-(IC5A-QA)") (class "Default")
      (node (ref "IC5") (pin "15") (pinfunction "QA_15") (pintype "tri_state"))
      (node (ref "R98") (pin "1") (pinfunction "1_1") (pintype "passive"))
    )
    (net (code "125") (name "Net-(IC5A-QB)") (class "Default")
      (node (ref "IC5") (pin "1") (pinfunction "QB_1") (pintype "tri_state"))
      (node (ref "R99") (pin "1") (pinfunction "1_1") (pintype "passive"))
    )
    (net (code "126") (name "Net-(IC5A-QC)") (class "Default")
      (node (ref "IC5") (pin "2") (pinfunction "QC_2") (pintype "tri_state"))
      (node (ref "R100") (pin "1") (pinfunction "1_1") (pintype "passive"))
    )
    (net (code "127") (name "Net-(IC5A-QD)") (class "Default")
      (node (ref "IC5") (pin "3") (pinfunction "QD_3") (pintype "tri_state"))
      (node (ref "R101") (pin "1") (pinfunction "1_1") (pintype "passive"))
    )
    (net (code "128") (name "Net-(IC5A-QE)") (class "Default")
      (node (ref "IC5") (pin "4") (pinfunction "QE_4") (pintype "tri_state"))
      (node (ref "R102") (pin "1") (pinfunction "1_1") (pintype "passive"))
    )
    (net (code "129") (name "Net-(IC5A-QF)") (class "Default")
      (node (ref "IC5") (pin "5") (pinfunction "QF_5") (pintype "tri_state"))
      (node (ref "R103") (pin "1") (pinfunction "1_1") (pintype "passive"))
    )
    (net (code "130") (name "Net-(IC5A-QG)") (class "Default")
      (node (ref "IC5") (pin "6") (pinfunction "QG_6") (pintype "tri_state"))
      (node (ref "R104") (pin "1") (pinfunction "1_1") (pintype "passive"))
    )
    (net (code "131") (name "Net-(IC5A-QH)") (class "Default")
      (node (ref "IC5") (pin "7") (pinfunction "QH_7") (pintype "tri_state"))
      (node (ref "R105") (pin "1") (pinfunction "1_1") (pintype "passive"))
    )
    (net (code "132") (name "Net-(IC5A-QH*)") (class "Default")
      (node (ref "IC5") (pin "9") (pinfunction "QH*_9") (pintype "tri_state"))
      (node (ref "IC6") (pin "14") (pinfunction "SER_14") (pintype "input"))
    )
    (net (code "133") (name "Net-(IC6A-QA)") (class "Default")
      (node (ref "IC6") (pin "15") (pinfunction "QA_15") (pintype "tri_state"))
      (node (ref "R106") (pin "1") (pinfunction "1_1") (pintype "passive"))
    )
    (net (code "134") (name "Net-(IC6A-QB)") (class "Default")
      (node (ref "IC6") (pin "1") (pinfunction "QB_1") (pintype "tri_state"))
      (node (ref "R107") (pin "1") (pinfunction "1_1") (pintype "passive"))
    )
    (net (code "135") (name "Net-(IC6A-QC)") (class "Default")
      (node (ref "IC6") (pin "2") (pinfunction "QC_2") (pintype "tri_state"))
      (node (ref "R108") (pin "1") (pinfunction "1_1") (pintype "passive"))
    )
    (net (code "136") (name "Net-(IC6A-QD)") (class "Default")
      (node (ref "IC6") (pin "3") (pinfunction "QD_3") (pintype "tri_state"))
      (node (ref "R109") (pin "1") (pinfunction "1_1") (pintype "passive"))
    )
    (net (code "137") (name "Net-(IC6A-QE)") (class "Default")
      (node (ref "IC6") (pin "4") (pinfunction "QE_4") (pintype "tri_state"))
      (node (ref "R110") (pin "1") (pinfunction "1_1") (pintype "passive"))
    )
    (net (code "138") (name "Net-(IC6A-QF)") (class "Default")
      (node (ref "IC6") (pin "5") (pinfunction "QF_5") (pintype "tri_state"))
      (node (ref "R111") (pin "1") (pinfunction "1_1") (pintype "passive"))
    )
    (net (code "139") (name "Net-(IC6A-QG)") (class "Default")
      (node (ref "IC6") (pin "6") (pinfunction "QG_6") (pintype "tri_state"))
      (node (ref "R112") (pin "1") (pinfunction "1_1") (pintype "passive"))
    )
    (net (code "140") (name "Net-(IC6A-QH)") (class "Default")
      (node (ref "IC6") (pin "7") (pinfunction "QH_7") (pintype "tri_state"))
      (node (ref "R113") (pin "1") (pinfunction "1_1") (pintype "passive"))
    )
    (net (code "141") (name "Net-(IC6A-QH*)") (class "Default")
      (node (ref "IC6") (pin "9") (pinfunction "QH*_9") (pintype "tri_state"))
      (node (ref "IC7") (pin "14") (pinfunction "SER_14") (pintype "input"))
    )
    (net (code "142") (name "Net-(IC7A-QA)") (class "Default")
      (node (ref "IC7") (pin "15") (pinfunction "QA_15") (pintype "tri_state"))
      (node (ref "R114") (pin "1") (pinfunction "1_1") (pintype "passive"))
    )
    (net (code "143") (name "Net-(IC7A-QB)") (class "Default")
      (node (ref "IC7") (pin "1") (pinfunction "QB_1") (pintype "tri_state"))
      (node (ref "R115") (pin "1") (pinfunction "1_1") (pintype "passive"))
    )
    (net (code "144") (name "Net-(IC7A-QC)") (class "Default")
      (node (ref "IC7") (pin "2") (pinfunction "QC_2") (pintype "tri_state"))
      (node (ref "R116") (pin "1") (pinfunction "1_1") (pintype "passive"))
    )
    (net (code "145") (name "Net-(IC7A-QD)") (class "Default")
      (node (ref "IC7") (pin "3") (pinfunction "QD_3") (pintype "tri_state"))
      (node (ref "R117") (pin "1") (pinfunction "1_1") (pintype "passive"))
    )
    (net (code "146") (name "Net-(IC7A-QE)") (class "Default")
      (node (ref "IC7") (pin "4") (pinfunction "QE_4") (pintype "tri_state"))
      (node (ref "R118") (pin "1") (pinfunction "1_1") (pintype "passive"))
    )
    (net (code "147") (name "Net-(IC7A-QF)") (class "Default")
      (node (ref "IC7") (pin "5") (pinfunction "QF_5") (pintype "tri_state"))
      (node (ref "R119") (pin "1") (pinfunction "1_1") (pintype "passive"))
    )
    (net (code "148") (name "Net-(IC7A-QG)") (class "Default")
      (node (ref "IC7") (pin "6") (pinfunction "QG_6") (pintype "tri_state"))
      (node (ref "R120") (pin "1") (pinfunction "1_1") (pintype "passive"))
    )
    (net (code "149") (name "Net-(IC7A-QH)") (class "Default")
      (node (ref "IC7") (pin "7") (pinfunction "QH_7") (pintype "tri_state"))
      (node (ref "R121") (pin "1") (pinfunction "1_1") (pintype "passive"))
    )
    (net (code "150") (name "Net-(IC7A-QH*)") (class "Default")
      (node (ref "IC7") (pin "9") (pinfunction "QH*_9") (pintype "tri_state"))
      (node (ref "IC8") (pin "14") (pinfunction "SER_14") (pintype "input"))
    )
    (net (code "151") (name "Net-(IC8A-QA)") (class "Default")
      (node (ref "IC8") (pin "15") (pinfunction "QA_15") (pintype "tri_state"))
      (node (ref "R122") (pin "1") (pinfunction "1_1") (pintype "passive"))
    )
    (net (code "152") (name "Net-(IC8A-QB)") (class "Default")
      (node (ref "IC8") (pin "1") (pinfunction "QB_1") (pintype "tri_state"))
      (node (ref "R123") (pin "1") (pinfunction "1_1") (pintype "passive"))
    )
    (net (code "153") (name "Net-(IC8A-QC)") (class "Default")
      (node (ref "IC8") (pin "2") (pinfunction "QC_2") (pintype "tri_state"))
      (node (ref "R124") (pin "1") (pinfunction "1_1") (pintype "passive"))
    )
    (net (code "154") (name "Net-(IC8A-QD)") (class "Default")
      (node (ref "IC8") (pin "3") (pinfunction "QD_3") (pintype "tri_state"))
      (node (ref "R125") (pin "1") (pinfunction "1_1") (pintype "passive"))
    )
    (net (code "155") (name "Net-(IC8A-QE)") (class "Default")
      (node (ref "IC8") (pin "4") (pinfunction "QE_4") (pintype "tri_state"))
      (node (ref "R126") (pin "1") (pinfunction "1_1") (pintype "passive"))
    )
    (net (code "156") (name "Net-(IC8A-QF)") (class "Default")
      (node (ref "IC8") (pin "5") (pinfunction "QF_5") (pintype "tri_state"))
      (node (ref "R127") (pin "1") (pinfunction "1_1") (pintype "passive"))
    )
    (net (code "157") (name "Net-(IC9A-QA)") (class "Default")
      (node (ref "IC9") (pin "15") (pinfunction "QA_15") (pintype "tri_state"))
      (node (ref "R67") (pin "1") (pinfunction "1_1") (pintype "passive"))
    )
    (net (code "158") (name "Net-(IC9A-QB)") (class "Default")
      (node (ref "IC9") (pin "1") (pinfunction "QB_1") (pintype "tri_state"))
      (node (ref "R68") (pin "1") (pinfunction "1_1") (pintype "passive"))
    )
    (net (code "159") (name "Net-(IC9A-QC)") (class "Default")
      (node (ref "IC9") (pin "2") (pinfunction "QC_2") (pintype "tri_state"))
      (node (ref "R69") (pin "1") (pinfunction "1_1") (pintype "passive"))
    )
    (net (code "160") (name "Net-(IC9A-QD)") (class "Default")
      (node (ref "IC9") (pin "3") (pinfunction "QD_3") (pintype "tri_state"))
      (node (ref "R70") (pin "1") (pinfunction "1_1") (pintype "passive"))
    )
    (net (code "161") (name "Net-(IC9A-QE)") (class "Default")
      (node (ref "IC9") (pin "4") (pinfunction "QE_4") (pintype "tri_state"))
      (node (ref "R71") (pin "1") (pinfunction "1_1") (pintype "passive"))
    )
    (net (code "162") (name "Net-(IC9A-QF)") (class "Default")
      (node (ref "IC9") (pin "5") (pinfunction "QF_5") (pintype "tri_state"))
      (node (ref "R72") (pin "1") (pinfunction "1_1") (pintype "passive"))
    )
    (net (code "163") (name "Net-(IC9A-QG)") (class "Default")
      (node (ref "IC9") (pin "6") (pinfunction "QG_6") (pintype "tri_state"))
      (node (ref "R73") (pin "1") (pinfunction "1_1") (pintype "passive"))
    )
    (net (code "164") (name "Net-(IC9A-QH)") (class "Default")
      (node (ref "IC9") (pin "7") (pinfunction "QH_7") (pintype "tri_state"))
      (node (ref "R74") (pin "1") (pinfunction "1_1") (pintype "passive"))
    )
    (net (code "165") (name "Net-(IC10A-QA)") (class "Default")
      (node (ref "IC10") (pin "15") (pinfunction "QA_15") (pintype "tri_state"))
      (node (ref "R75") (pin "1") (pinfunction "1_1") (pintype "passive"))
    )
    (net (code "166") (name "Net-(IC10A-QB)") (class "Default")
      (node (ref "IC10") (pin "1") (pinfunction "QB_1") (pintype "tri_state"))
      (node (ref "R76") (pin "1") (pinfunction "1_1") (pintype "passive"))
    )
    (net (code "167") (name "Net-(IC10A-QC)") (class "Default")
      (node (ref "IC10") (pin "2") (pinfunction "QC_2") (pintype "tri_state"))
      (node (ref "R77") (pin "1") (pinfunction "1_1") (pintype "passive"))
    )
    (net (code "168") (name "Net-(IC10A-QD)") (class "Default")
      (node (ref "IC10") (pin "3") (pinfunction "QD_3") (pintype "tri_state"))
      (node (ref "R78") (pin "1") (pinfunction "1_1") (pintype "passive"))
    )
    (net (code "169") (name "Net-(IC10A-QE)") (class "Default")
      (node (ref "IC10") (pin "4") (pinfunction "QE_4") (pintype "tri_state"))
      (node (ref "R79") (pin "1") (pinfunction "1_1") (pintype "passive"))
    )
    (net (code "170") (name "Net-(IC10A-QF)") (class "Default")
      (node (ref "IC10") (pin "5") (pinfunction "QF_5") (pintype "tri_state"))
      (node (ref "R80") (pin "1") (pinfunction "1_1") (pintype "passive"))
    )
    (net (code "171") (name "Net-(IC10A-QG)") (class "Default")
      (node (ref "IC10") (pin "6") (pinfunction "QG_6") (pintype "tri_state"))
      (node (ref "R81") (pin "1") (pinfunction "1_1") (pintype "passive"))
    )
    (net (code "172") (name "Net-(IC10A-QH)") (class "Default")
      (node (ref "IC10") (pin "7") (pinfunction "QH_7") (pintype "tri_state"))
      (node (ref "R82") (pin "1") (pinfunction "1_1") (pintype "passive"))
    )
    (net (code "173") (name "Net-(IC10A-QH*)") (class "Default")
      (node (ref "IC10") (pin "9") (pinfunction "QH*_9") (pintype "tri_state"))
      (node (ref "IC11") (pin "14") (pinfunction "SER_14") (pintype "input"))
    )
    (net (code "174") (name "Net-(IC10A-SER)") (class "Default")
      (node (ref "IC10") (pin "14") (pinfunction "SER_14") (pintype "input"))
      (node (ref "IC9") (pin "9") (pinfunction "QH*_9") (pintype "tri_state"))
    )
    (net (code "175") (name "Net-(IC11A-QA)") (class "Default")
      (node (ref "IC11") (pin "15") (pinfunction "QA_15") (pintype "tri_state"))
      (node (ref "R83") (pin "1") (pinfunction "1_1") (pintype "passive"))
    )
    (net (code "176") (name "Net-(IC11A-QB)") (class "Default")
      (node (ref "IC11") (pin "1") (pinfunction "QB_1") (pintype "tri_state"))
      (node (ref "R84") (pin "1") (pinfunction "1_1") (pintype "passive"))
    )
    (net (code "177") (name "Net-(IC11A-QC)") (class "Default")
      (node (ref "IC11") (pin "2") (pinfunction "QC_2") (pintype "tri_state"))
      (node (ref "R85") (pin "1") (pinfunction "1_1") (pintype "passive"))
    )
    (net (code "178") (name "Net-(IC11A-QD)") (class "Default")
      (node (ref "IC11") (pin "3") (pinfunction "QD_3") (pintype "tri_state"))
      (node (ref "R86") (pin "1") (pinfunction "1_1") (pintype "passive"))
    )
    (net (code "179") (name "Net-(IC11A-QE)") (class "Default")
      (node (ref "IC11") (pin "4") (pinfunction "QE_4") (pintype "tri_state"))
      (node (ref "R87") (pin "1") (pinfunction "1_1") (pintype "passive"))
    )
    (net (code "180") (name "Net-(IC11A-QF)") (class "Default")
      (node (ref "IC11") (pin "5") (pinfunction "QF_5") (pintype "tri_state"))
      (node (ref "R88") (pin "1") (pinfunction "1_1") (pintype "passive"))
    )
    (net (code "181") (name "Net-(IC11A-QG)") (class "Default")
      (node (ref "IC11") (pin "6") (pinfunction "QG_6") (pintype "tri_state"))
      (node (ref "R89") (pin "1") (pinfunction "1_1") (pintype "passive"))
    )
    (net (code "182") (name "Net-(IC11A-QH)") (class "Default")
      (node (ref "IC11") (pin "7") (pinfunction "QH_7") (pintype "tri_state"))
      (node (ref "R90") (pin "1") (pinfunction "1_1") (pintype "passive"))
    )
    (net (code "183") (name "Net-(IC11A-QH*)") (class "Default")
      (node (ref "IC11") (pin "9") (pinfunction "QH*_9") (pintype "tri_state"))
      (node (ref "IC12") (pin "14") (pinfunction "SER_14") (pintype "input"))
    )
    (net (code "184") (name "Net-(IC12A-QA)") (class "Default")
      (node (ref "IC12") (pin "15") (pinfunction "QA_15") (pintype "tri_state"))
      (node (ref "R91") (pin "1") (pinfunction "1_1") (pintype "passive"))
    )
    (net (code "185") (name "Net-(IC12A-QB)") (class "Default")
      (node (ref "IC12") (pin "1") (pinfunction "QB_1") (pintype "tri_state"))
      (node (ref "R92") (pin "1") (pinfunction "1_1") (pintype "passive"))
    )
    (net (code "186") (name "Net-(IC12A-QC)") (class "Default")
      (node (ref "IC12") (pin "2") (pinfunction "QC_2") (pintype "tri_state"))
      (node (ref "R93") (pin "1") (pinfunction "1_1") (pintype "passive"))
    )
    (net (code "187") (name "Net-(IC12A-QD)") (class "Default")
      (node (ref "IC12") (pin "3") (pinfunction "QD_3") (pintype "tri_state"))
      (node (ref "R94") (pin "1") (pinfunction "1_1") (pintype "passive"))
    )
    (net (code "188") (name "Net-(IC12A-QE)") (class "Default")
      (node (ref "IC12") (pin "4") (pinfunction "QE_4") (pintype "tri_state"))
      (node (ref "R95") (pin "1") (pinfunction "1_1") (pintype "passive"))
    )
    (net (code "189") (name "Net-(IC12A-QF)") (class "Default")
      (node (ref "IC12") (pin "5") (pinfunction "QF_5") (pintype "tri_state"))
      (node (ref "R96") (pin "1") (pinfunction "1_1") (pintype "passive"))
    )
    (net (code "190") (name "Net-(IC12A-QH)") (class "Default")
      (node (ref "IC12") (pin "7") (pinfunction "QH_7") (pintype "tri_state"))
      (node (ref "R97") (pin "1") (pinfunction "1_1") (pintype "passive"))
    )
    (net (code "191") (name "Net-(IC12A-QH*)") (class "Default")
      (node (ref "IC12") (pin "9") (pinfunction "QH*_9") (pintype "tri_state"))
      (node (ref "IC13") (pin "14") (pinfunction "SER_14") (pintype "input"))
    )
    (net (code "192") (name "Net-(IC13A-QA)") (class "Default")
      (node (ref "IC13") (pin "15") (pinfunction "QA_15") (pintype "tri_state"))
      (node (ref "R51") (pin "1") (pinfunction "1_1") (pintype "passive"))
    )
    (net (code "193") (name "Net-(IC13A-QB)") (class "Default")
      (node (ref "IC13") (pin "1") (pinfunction "QB_1") (pintype "tri_state"))
      (node (ref "R52") (pin "1") (pinfunction "1_1") (pintype "passive"))
    )
    (net (code "194") (name "Net-(IC13A-QC)") (class "Default")
      (node (ref "IC13") (pin "2") (pinfunction "QC_2") (pintype "tri_state"))
      (node (ref "R53") (pin "1") (pinfunction "1_1") (pintype "passive"))
    )
    (net (code "195") (name "Net-(IC13A-QD)") (class "Default")
      (node (ref "IC13") (pin "3") (pinfunction "QD_3") (pintype "tri_state"))
      (node (ref "R54") (pin "1") (pinfunction "1_1") (pintype "passive"))
    )
    (net (code "196") (name "Net-(IC13A-QE)") (class "Default")
      (node (ref "IC13") (pin "4") (pinfunction "QE_4") (pintype "tri_state"))
      (node (ref "R55") (pin "1") (pinfunction "1_1") (pintype "passive"))
    )
    (net (code "197") (name "Net-(IC13A-QF)") (class "Default")
      (node (ref "IC13") (pin "5") (pinfunction "QF_5") (pintype "tri_state"))
      (node (ref "R56") (pin "1") (pinfunction "1_1") (pintype "passive"))
    )
    (net (code "198") (name "Net-(IC13A-QG)") (class "Default")
      (node (ref "IC13") (pin "6") (pinfunction "QG_6") (pintype "tri_state"))
      (node (ref "R57") (pin "1") (pinfunction "1_1") (pintype "passive"))
    )
    (net (code "199") (name "Net-(IC13A-QH)") (class "Default")
      (node (ref "IC13") (pin "7") (pinfunction "QH_7") (pintype "tri_state"))
      (node (ref "R58") (pin "1") (pinfunction "1_1") (pintype "passive"))
    )
    (net (code "200") (name "Net-(IC13A-QH*)") (class "Default")
      (node (ref "IC13") (pin "9") (pinfunction "QH*_9") (pintype "tri_state"))
      (node (ref "IC16") (pin "14") (pinfunction "SER_14") (pintype "input"))
    )
    (net (code "201") (name "Net-(IC14A-QH)") (class "Default")
      (node (ref "IC14") (pin "9") (pinfunction "QH_9") (pintype "output"))
      (node (ref "IC15") (pin "10") (pinfunction "SER_10") (pintype "input"))
    )
    (net (code "202") (name "Net-(IC15A-QH)") (class "Default")
      (node (ref "IC15") (pin "9") (pinfunction "QH_9") (pintype "output"))
      (node (ref "IC2") (pin "10") (pinfunction "SER_10") (pintype "input"))
    )
    (net (code "203") (name "Net-(IC16A-QA)") (class "Default")
      (node (ref "IC16") (pin "15") (pinfunction "QA_15") (pintype "tri_state"))
      (node (ref "R59") (pin "1") (pinfunction "1_1") (pintype "passive"))
    )
    (net (code "204") (name "Net-(IC16A-QB)") (class "Default")
      (node (ref "IC16") (pin "1") (pinfunction "QB_1") (pintype "tri_state"))
      (node (ref "R60") (pin "1") (pinfunction "1_1") (pintype "passive"))
    )
    (net (code "205") (name "Net-(IC16A-QC)") (class "Default")
      (node (ref "IC16") (pin "2") (pinfunction "QC_2") (pintype "tri_state"))
      (node (ref "R61") (pin "1") (pinfunction "1_1") (pintype "passive"))
    )
    (net (code "206") (name "Net-(IC16A-QD)") (class "Default")
      (node (ref "IC16") (pin "3") (pinfunction "QD_3") (pintype "tri_state"))
      (node (ref "R62") (pin "1") (pinfunction "1_1") (pintype "passive"))
    )
    (net (code "207") (name "Net-(IC16A-QE)") (class "Default")
      (node (ref "IC16") (pin "4") (pinfunction "QE_4") (pintype "tri_state"))
      (node (ref "R63") (pin "1") (pinfunction "1_1") (pintype "passive"))
    )
    (net (code "208") (name "Net-(IC16A-QF)") (class "Default")
      (node (ref "IC16") (pin "5") (pinfunction "QF_5") (pintype "tri_state"))
      (node (ref "R64") (pin "1") (pinfunction "1_1") (pintype "passive"))
    )
    (net (code "209") (name "Net-(IC16A-QG)") (class "Default")
      (node (ref "IC16") (pin "6") (pinfunction "QG_6") (pintype "tri_state"))
      (node (ref "R65") (pin "1") (pinfunction "1_1") (pintype "passive"))
    )
    (net (code "210") (name "Net-(IC16A-QH)") (class "Default")
      (node (ref "IC16") (pin "7") (pinfunction "QH_7") (pintype "tri_state"))
      (node (ref "R66") (pin "1") (pinfunction "1_1") (pintype "passive"))
    )
    (net (code "211") (name "Net-(IC16A-QH*)") (class "Default")
      (node (ref "IC16") (pin "9") (pinfunction "QH*_9") (pintype "tri_state"))
      (node (ref "IC19") (pin "5") (pinfunction "I1_5") (pintype "input"))
    )
    (net (code "212") (name "Net-(IC17B-Y2)") (class "Default")
      (node (ref "IC17") (pin "7") (pinfunction "Y2_7") (pintype "tri_state"))
      (node (ref "R11") (pin "1") (pinfunction "1_1") (pintype "passive"))
    )
    (net (code "213") (name "Net-(IC18A-SER)") (class "Default")
      (node (ref "IC18") (pin "10") (pinfunction "SER_10") (pintype "input"))
      (node (ref "IC2") (pin "9") (pinfunction "QH_9") (pintype "output"))
    )
    (net (code "214") (name "Net-(IC19A-O)") (class "Default")
      (node (ref "IC19") (pin "3") (pinfunction "O_3") (pintype "output"))
      (node (ref "IC19") (pin "4") (pinfunction "I0_4") (pintype "input"))
    )
    (net (code "215") (name "Net-(IDE-Pad21)") (class "Default")
      (node (ref "IDE") (pin "21") (pinfunction "21_21") (pintype "passive"))
      (node (ref "R12") (pin "2") (pinfunction "2_2") (pintype "passive"))
    )
    (net (code "216") (name "Net-(IDE-Pad23)") (class "Default")
      (node (ref "IDE") (pin "23") (pinfunction "23_23") (pintype "passive"))
      (node (ref "R13") (pin "2") (pinfunction "2_2") (pintype "passive"))
    )
    (net (code "217") (name "Net-(IDE-Pad25)") (class "Default")
      (node (ref "IDE") (pin "25") (pinfunction "25_25") (pintype "passive"))
      (node (ref "R14") (pin "2") (pinfunction "2_2") (pintype "passive"))
    )
    (net (code "218") (name "Net-(IDE-Pad27)") (class "Default")
      (node (ref "IDE") (pin "27") (pinfunction "27_27") (pintype "passive"))
      (node (ref "R15") (pin "2") (pinfunction "2_2") (pintype "passive"))
    )
    (net (code "219") (name "Net-(IDE-Pad31)") (class "Default")
      (node (ref "IDE") (pin "31") (pinfunction "31_31") (pintype "passive"))
      (node (ref "R16") (pin "2") (pinfunction "2_2") (pintype "passive"))
    )
    (net (code "220") (name "Net-(R21-Pad2)") (class "Default")
      (node (ref "R21") (pin "2") (pinfunction "2_2") (pintype "passive"))
      (node (ref "SLOT1") (pin "31") (pinfunction "31_31") (pintype "passive"))
    )
    (net (code "221") (name "Net-(R22-Pad2)") (class "Default")
      (node (ref "R22") (pin "2") (pinfunction "2_2") (pintype "passive"))
      (node (ref "SLOT2") (pin "31") (pinfunction "31_31") (pintype "passive"))
    )
    (net (code "222") (name "OPR") (class "Default")
      (node (ref "D40") (pin "16") (pinfunction "16_16") (pintype "passive"))
      (node (ref "R58") (pin "2") (pinfunction "2_2") (pintype "passive"))
    )
    (net (code "223") (name "PAUSE") (class "Default")
      (node (ref "D40") (pin "31") (pinfunction "31_31") (pintype "passive"))
      (node (ref "R60") (pin "2") (pinfunction "2_2") (pintype "passive"))
    )
    (net (code "224") (name "PB-A0") (class "Default")
      (node (ref "IDE") (pin "35") (pinfunction "35_35") (pintype "passive"))
      (node (ref "SLOT1") (pin "35") (pinfunction "35_35") (pintype "passive"))
      (node (ref "SLOT2") (pin "35") (pinfunction "35_35") (pintype "passive"))
      (node (ref "XESS") (pin "57") (pinfunction "L5_57") (pintype "bidirectional"))
    )
    (net (code "225") (name "PB-A1") (class "Default")
      (node (ref "IDE") (pin "33") (pinfunction "33_33") (pintype "passive"))
      (node (ref "SLOT1") (pin "33") (pinfunction "33_33") (pintype "passive"))
      (node (ref "SLOT2") (pin "33") (pinfunction "33_33") (pintype "passive"))
      (node (ref "XESS") (pin "56") (pinfunction "N2_56") (pintype "bidirectional"))
    )
    (net (code "226") (name "PB-A2") (class "Default")
      (node (ref "IDE") (pin "36") (pinfunction "36_36") (pintype "passive"))
      (node (ref "SLOT1") (pin "36") (pinfunction "36_36") (pintype "passive"))
      (node (ref "SLOT2") (pin "36") (pinfunction "36_36") (pintype "passive"))
      (node (ref "XESS") (pin "51") (pinfunction "M3_51") (pintype "bidirectional"))
    )
    (net (code "227") (name "PB-A3") (class "Default")
      (node (ref "SLOT1") (pin "38") (pinfunction "38_38") (pintype "passive"))
      (node (ref "SLOT2") (pin "38") (pinfunction "38_38") (pintype "passive"))
      (node (ref "XESS") (pin "50") (pinfunction "N1_50") (pintype "bidirectional"))
    )
    (net (code "228") (name "PB-A4") (class "Default")
      (node (ref "SLOT1") (pin "39") (pinfunction "39_39") (pintype "passive"))
      (node (ref "SLOT2") (pin "39") (pinfunction "39_39") (pintype "passive"))
      (node (ref "XESS") (pin "70") (pinfunction "T13_70") (pintype "bidirectional"))
    )
    (net (code "229") (name "PB-D0") (class "Default")
      (node (ref "IDE") (pin "17") (pinfunction "17_17") (pintype "passive"))
      (node (ref "SLOT1") (pin "17") (pinfunction "17_17") (pintype "passive"))
      (node (ref "SLOT2") (pin "17") (pinfunction "17_17") (pintype "passive"))
      (node (ref "XESS") (pin "71") (pinfunction "P12_71") (pintype "bidirectional"))
    )
    (net (code "230") (name "PB-D1") (class "Default")
      (node (ref "IDE") (pin "15") (pinfunction "15_15") (pintype "passive"))
      (node (ref "SLOT1") (pin "15") (pinfunction "15_15") (pintype "passive"))
      (node (ref "SLOT2") (pin "15") (pinfunction "15_15") (pintype "passive"))
      (node (ref "XESS") (pin "40") (pinfunction "J1_40") (pintype "bidirectional"))
    )
    (net (code "231") (name "PB-D2") (class "Default")
      (node (ref "IDE") (pin "13") (pinfunction "13_13") (pintype "passive"))
      (node (ref "SLOT1") (pin "13") (pinfunction "13_13") (pintype "passive"))
      (node (ref "SLOT2") (pin "13") (pinfunction "13_13") (pintype "passive"))
      (node (ref "XESS") (pin "39") (pinfunction "H1_39") (pintype "bidirectional"))
    )
    (net (code "232") (name "PB-D3") (class "Default")
      (node (ref "IDE") (pin "11") (pinfunction "11_11") (pintype "passive"))
      (node (ref "SLOT1") (pin "11") (pinfunction "11_11") (pintype "passive"))
      (node (ref "SLOT2") (pin "11") (pinfunction "11_11") (pintype "passive"))
      (node (ref "XESS") (pin "38") (pinfunction "H3_38") (pintype "bidirectional"))
    )
    (net (code "233") (name "PB-D4") (class "Default")
      (node (ref "IDE") (pin "9") (pinfunction "9_9") (pintype "passive"))
      (node (ref "SLOT1") (pin "9") (pinfunction "9_9") (pintype "passive"))
      (node (ref "SLOT2") (pin "9") (pinfunction "9_9") (pintype "passive"))
      (node (ref "XESS") (pin "35") (pinfunction "G2_35") (pintype "bidirectional"))
    )
    (net (code "234") (name "PB-D5") (class "Default")
      (node (ref "IDE") (pin "7") (pinfunction "7_7") (pintype "passive"))
      (node (ref "SLOT1") (pin "7") (pinfunction "7_7") (pintype "passive"))
      (node (ref "SLOT2") (pin "7") (pinfunction "7_7") (pintype "passive"))
      (node (ref "XESS") (pin "80") (pinfunction "K15_80") (pintype "bidirectional"))
    )
    (net (code "235") (name "PB-D6") (class "Default")
      (node (ref "IDE") (pin "5") (pinfunction "5_5") (pintype "passive"))
      (node (ref "SLOT1") (pin "5") (pinfunction "5_5") (pintype "passive"))
      (node (ref "SLOT2") (pin "5") (pinfunction "5_5") (pintype "passive"))
      (node (ref "XESS") (pin "81") (pinfunction "K16_81") (pintype "bidirectional"))
    )
    (net (code "236") (name "PB-D7") (class "Default")
      (node (ref "IDE") (pin "3") (pinfunction "3_3") (pintype "passive"))
      (node (ref "SLOT1") (pin "3") (pinfunction "3_3") (pintype "passive"))
      (node (ref "SLOT2") (pin "3") (pinfunction "3_3") (pintype "passive"))
      (node (ref "XESS") (pin "10") (pinfunction "F15_10") (pintype "bidirectional"))
    )
    (net (code "237") (name "PB-D8") (class "Default")
      (node (ref "IDE") (pin "4") (pinfunction "4_4") (pintype "passive"))
      (node (ref "SLOT1") (pin "4") (pinfunction "4_4") (pintype "passive"))
      (node (ref "SLOT2") (pin "4") (pinfunction "4_4") (pintype "passive"))
      (node (ref "XESS") (pin "27") (pinfunction "E2_27") (pintype "bidirectional"))
    )
    (net (code "238") (name "PB-D9") (class "Default")
      (node (ref "IDE") (pin "6") (pinfunction "6_6") (pintype "passive"))
      (node (ref "SLOT1") (pin "6") (pinfunction "6_6") (pintype "passive"))
      (node (ref "SLOT2") (pin "6") (pinfunction "6_6") (pintype "passive"))
      (node (ref "XESS") (pin "28") (pinfunction "E1_28") (pintype "bidirectional"))
    )
    (net (code "239") (name "PB-D10") (class "Default")
      (node (ref "IDE") (pin "8") (pinfunction "8_8") (pintype "passive"))
      (node (ref "SLOT1") (pin "8") (pinfunction "8_8") (pintype "passive"))
      (node (ref "SLOT2") (pin "8") (pinfunction "8_8") (pintype "passive"))
      (node (ref "XESS") (pin "29") (pinfunction "F3_29") (pintype "bidirectional"))
    )
    (net (code "240") (name "PB-D11") (class "Default")
      (node (ref "IDE") (pin "10") (pinfunction "10_10") (pintype "passive"))
      (node (ref "SLOT1") (pin "10") (pinfunction "10_10") (pintype "passive"))
      (node (ref "SLOT2") (pin "10") (pinfunction "10_10") (pintype "passive"))
      (node (ref "XESS") (pin "32") (pinfunction "F2_32") (pintype "bidirectional"))
    )
    (net (code "241") (name "PB-D12") (class "Default")
      (node (ref "IDE") (pin "12") (pinfunction "12_12") (pintype "passive"))
      (node (ref "SLOT1") (pin "12") (pinfunction "12_12") (pintype "passive"))
      (node (ref "SLOT2") (pin "12") (pinfunction "12_12") (pintype "passive"))
      (node (ref "XESS") (pin "33") (pinfunction "G4_33") (pintype "bidirectional"))
    )
    (net (code "242") (name "PB-D13") (class "Default")
      (node (ref "IDE") (pin "14") (pinfunction "14_14") (pintype "passive"))
      (node (ref "SLOT1") (pin "14") (pinfunction "14_14") (pintype "passive"))
      (node (ref "SLOT2") (pin "14") (pinfunction "14_14") (pintype "passive"))
      (node (ref "XESS") (pin "34") (pinfunction "G3_34") (pintype "bidirectional"))
    )
    (net (code "243") (name "PB-D14") (class "Default")
      (node (ref "IDE") (pin "16") (pinfunction "16_16") (pintype "passive"))
      (node (ref "SLOT1") (pin "16") (pinfunction "16_16") (pintype "passive"))
      (node (ref "SLOT2") (pin "16") (pinfunction "16_16") (pintype "passive"))
      (node (ref "XESS") (pin "36") (pinfunction "G1_36") (pintype "bidirectional"))
    )
    (net (code "244") (name "PB-D15") (class "Default")
      (node (ref "IDE") (pin "18") (pinfunction "18_18") (pintype "passive"))
      (node (ref "SLOT1") (pin "18") (pinfunction "18_18") (pintype "passive"))
      (node (ref "SLOT2") (pin "18") (pinfunction "18_18") (pintype "passive"))
      (node (ref "XESS") (pin "37") (pinfunction "H4_37") (pintype "bidirectional"))
    )
    (net (code "245") (name "PB-RD#") (class "Default")
      (node (ref "R14") (pin "1") (pinfunction "1_1") (pintype "passive"))
      (node (ref "SLOT1") (pin "25") (pinfunction "25_25") (pintype "passive"))
      (node (ref "SLOT2") (pin "25") (pinfunction "25_25") (pintype "passive"))
      (node (ref "XESS") (pin "61") (pinfunction "P2_61") (pintype "bidirectional"))
    )
    (net (code "246") (name "PB-WR#") (class "Default")
      (node (ref "R13") (pin "1") (pinfunction "1_1") (pintype "passive"))
      (node (ref "SLOT1") (pin "23") (pinfunction "23_23") (pintype "passive"))
      (node (ref "SLOT2") (pin "23") (pinfunction "23_23") (pintype "passive"))
      (node (ref "XESS") (pin "62") (pinfunction "R1_62") (pintype "bidirectional"))
    )
    (net (code "247") (name "PC0") (class "Default")
      (node (ref "E40") (pin "1") (pinfunction "1_1") (pintype "passive"))
      (node (ref "R98") (pin "2") (pinfunction "2_2") (pintype "passive"))
    )
    (net (code "248") (name "PC1") (class "Default")
      (node (ref "E40") (pin "10") (pinfunction "10_10") (pintype "passive"))
      (node (ref "R103") (pin "2") (pinfunction "2_2") (pintype "passive"))
    )
    (net (code "249") (name "PC2") (class "Default")
      (node (ref "E40") (pin "11") (pinfunction "11_11") (pintype "passive"))
      (node (ref "R108") (pin "2") (pinfunction "2_2") (pintype "passive"))
    )
    (net (code "250") (name "PC3") (class "Default")
      (node (ref "E40") (pin "24") (pinfunction "24_24") (pintype "passive"))
      (node (ref "R113") (pin "2") (pinfunction "2_2") (pintype "passive"))
    )
    (net (code "251") (name "PC4") (class "Default")
      (node (ref "E40") (pin "25") (pinfunction "25_25") (pintype "passive"))
      (node (ref "R118") (pin "2") (pinfunction "2_2") (pintype "passive"))
    )
    (net (code "252") (name "PC5") (class "Default")
      (node (ref "E40") (pin "34") (pinfunction "34_34") (pintype "passive"))
      (node (ref "R123") (pin "2") (pinfunction "2_2") (pintype "passive"))
    )
    (net (code "253") (name "PC6") (class "Default")
      (node (ref "F40") (pin "1") (pinfunction "1_1") (pintype "passive"))
      (node (ref "R67") (pin "2") (pinfunction "2_2") (pintype "passive"))
    )
    (net (code "254") (name "PC7") (class "Default")
      (node (ref "F40") (pin "10") (pinfunction "10_10") (pintype "passive"))
      (node (ref "R72") (pin "2") (pinfunction "2_2") (pintype "passive"))
    )
    (net (code "255") (name "PC8") (class "Default")
      (node (ref "F40") (pin "11") (pinfunction "11_11") (pintype "passive"))
      (node (ref "R77") (pin "2") (pinfunction "2_2") (pintype "passive"))
    )
    (net (code "256") (name "PC9") (class "Default")
      (node (ref "F40") (pin "24") (pinfunction "24_24") (pintype "passive"))
      (node (ref "R82") (pin "2") (pinfunction "2_2") (pintype "passive"))
    )
    (net (code "257") (name "PC10") (class "Default")
      (node (ref "F40") (pin "25") (pinfunction "25_25") (pintype "passive"))
      (node (ref "R87") (pin "2") (pinfunction "2_2") (pintype "passive"))
    )
    (net (code "258") (name "PC11") (class "Default")
      (node (ref "F40") (pin "34") (pinfunction "34_34") (pintype "passive"))
      (node (ref "R92") (pin "2") (pinfunction "2_2") (pintype "passive"))
    )
    (net (code "259") (name "RCK") (class "Default")
      (node (ref "IC1") (pin "12") (pinfunction "RCK_12") (pintype "input"))
      (node (ref "IC10") (pin "12") (pinfunction "RCK_12") (pintype "input"))
      (node (ref "IC11") (pin "12") (pinfunction "RCK_12") (pintype "input"))
      (node (ref "IC12") (pin "12") (pinfunction "RCK_12") (pintype "input"))
      (node (ref "IC13") (pin "12") (pinfunction "RCK_12") (pintype "input"))
      (node (ref "IC16") (pin "12") (pinfunction "RCK_12") (pintype "input"))
      (node (ref "IC19") (pin "6") (pinfunction "O_6") (pintype "output"))
      (node (ref "IC4") (pin "12") (pinfunction "RCK_12") (pintype "input"))
      (node (ref "IC5") (pin "12") (pinfunction "RCK_12") (pintype "input"))
      (node (ref "IC6") (pin "12") (pinfunction "RCK_12") (pintype "input"))
      (node (ref "IC7") (pin "12") (pinfunction "RCK_12") (pintype "input"))
      (node (ref "IC8") (pin "12") (pinfunction "RCK_12") (pintype "input"))
      (node (ref "IC9") (pin "12") (pinfunction "RCK_12") (pintype "input"))
      (node (ref "SV1") (pin "7") (pinfunction "7_7") (pintype "passive"))
      (node (ref "SV2") (pin "7") (pinfunction "7_7") (pintype "passive"))
    )
    (net (code "260") (name "RESET-TRIG#") (class "Default")
      (node (ref "R23") (pin "1") (pinfunction "1_1") (pintype "passive"))
      (node (ref "XESS") (pin "21") (pinfunction "D15_21") (pintype "bidirectional"))
    )
    (net (code "261") (name "RS232-RD") (class "Default")
      (node (ref "D1") (pin "C") (pinfunction "C_C") (pintype "passive"))
      (node (ref "R2") (pin "1") (pinfunction "1_1") (pintype "passive"))
      (node (ref "XESS") (pin "31") (pinfunction "G5_31") (pintype "bidirectional"))
    )
    (net (code "262") (name "RS232-RTS") (class "Default")
      (node (ref "R3") (pin "1") (pinfunction "1_1") (pintype "passive"))
      (node (ref "XESS") (pin "26") (pinfunction "F4_26") (pintype "bidirectional"))
    )
    (net (code "263") (name "RS232-TD") (class "Default")
      (node (ref "R1") (pin "1") (pinfunction "1_1") (pintype "passive"))
      (node (ref "XESS") (pin "41") (pinfunction "J2_41") (pintype "bidirectional"))
    )
    (net (code "264") (name "RTS") (class "Default")
      (node (ref "IC3") (pin "7") (pinfunction "T2OUT_7") (pintype "output"))
      (node (ref "RS-232") (pin "5") (pinfunction "5_5") (pintype "passive"))
      (node (ref "X1") (pin "8") (pinfunction "F_8") (pintype "passive"))
    )
    (net (code "265") (name "RUN") (class "Default")
      (node (ref "D40") (pin "33") (pinfunction "33_33") (pintype "passive"))
      (node (ref "R61") (pin "2") (pinfunction "2_2") (pintype "passive"))
    )
    (net (code "266") (name "RXD") (class "Default")
      (node (ref "IC3") (pin "8") (pinfunction "R2IN_8") (pintype "input"))
      (node (ref "RS-232") (pin "4") (pinfunction "4_4") (pintype "passive"))
      (node (ref "X1") (pin "3") (pinfunction "F_3") (pintype "passive"))
    )
    (net (code "267") (name "SC0") (class "Default")
      (node (ref "C40") (pin "9") (pinfunction "9_9") (pintype "passive"))
      (node (ref "R129") (pin "2") (pinfunction "2_2") (pintype "passive"))
    )
    (net (code "268") (name "SC1") (class "Default")
      (node (ref "C40") (pin "2") (pinfunction "2_2") (pintype "passive"))
      (node (ref "R131") (pin "2") (pinfunction "2_2") (pintype "passive"))
    )
    (net (code "269") (name "SC2") (class "Default")
      (node (ref "C40") (pin "23") (pinfunction "23_23") (pintype "passive"))
      (node (ref "R133") (pin "2") (pinfunction "2_2") (pintype "passive"))
    )
    (net (code "270") (name "SC3") (class "Default")
      (node (ref "C40") (pin "12") (pinfunction "12_12") (pintype "passive"))
      (node (ref "R135") (pin "2") (pinfunction "2_2") (pintype "passive"))
    )
    (net (code "271") (name "SC4") (class "Default")
      (node (ref "C40") (pin "33") (pinfunction "33_33") (pintype "passive"))
      (node (ref "R137") (pin "2") (pinfunction "2_2") (pintype "passive"))
    )
    (net (code "272") (name "SCLK") (class "Default")
      (node (ref "IC14") (pin "2") (pinfunction "CLK_2") (pintype "input"))
      (node (ref "IC15") (pin "2") (pinfunction "CLK_2") (pintype "input"))
      (node (ref "IC17") (pin "5") (pinfunction "Y3_5") (pintype "tri_state"))
      (node (ref "IC18") (pin "2") (pinfunction "CLK_2") (pintype "input"))
      (node (ref "IC2") (pin "2") (pinfunction "CLK_2") (pintype "input"))
      (node (ref "SV1") (pin "10") (pinfunction "10_10") (pintype "passive"))
      (node (ref "SV2") (pin "10") (pinfunction "10_10") (pintype "passive"))
    )
    (net (code "273") (name "SD-CD#") (class "Default")
      (node (ref "J4") (pin "10") (pinfunction "CD#_10") (pintype "output"))
      (node (ref "R4") (pin "1") (pinfunction "1_1") (pintype "passive"))
      (node (ref "XESS") (pin "4") (pinfunction "H14_4") (pintype "bidirectional"))
    )
    (net (code "274") (name "SD-CLK") (class "Default")
      (node (ref "J4") (pin "5") (pinfunction "CLK/SCLK_5") (pintype "bidirectional"))
      (node (ref "XESS") (pin "1") (pinfunction "H16_1") (pintype "bidirectional"))
    )
    (net (code "275") (name "SD-CMD") (class "Default")
      (node (ref "J4") (pin "2") (pinfunction "CMD/DI_2") (pintype "bidirectional"))
      (node (ref "XESS") (pin "45") (pinfunction "K5_45") (pintype "bidirectional"))
    )
    (net (code "276") (name "SD-DAT0") (class "Default")
      (node (ref "J4") (pin "7") (pinfunction "DAT0_7") (pintype "bidirectional"))
      (node (ref "XESS") (pin "66") (pinfunction "M10_66") (pintype "bidirectional"))
    )
    (net (code "277") (name "SD-DAT1") (class "Default")
      (node (ref "J4") (pin "8") (pinfunction "DAT1_8") (pintype "bidirectional"))
      (node (ref "XESS") (pin "67") (pinfunction "P11_67") (pintype "bidirectional"))
    )
    (net (code "278") (name "SD-DAT2") (class "Default")
      (node (ref "J4") (pin "9") (pinfunction "DAT2_9") (pintype "bidirectional"))
      (node (ref "XESS") (pin "68") (pinfunction "T12_68") (pintype "bidirectional"))
    )
    (net (code "279") (name "SD-DAT3") (class "Default")
      (node (ref "J4") (pin "1") (pinfunction "CD/DAT3_1") (pintype "bidirectional"))
      (node (ref "XESS") (pin "69") (pinfunction "R12_69") (pintype "bidirectional"))
    )
    (net (code "280") (name "SD-WP") (class "Default")
      (node (ref "J4") (pin "12") (pinfunction "WP_12") (pintype "output"))
      (node (ref "R5") (pin "1") (pinfunction "1_1") (pintype "passive"))
      (node (ref "XESS") (pin "5") (pinfunction "H13_5") (pintype "bidirectional"))
    )
    (net (code "281") (name "SDF0") (class "Default")
      (node (ref "A40") (pin "6") (pinfunction "6_6") (pintype "passive"))
      (node (ref "IC14") (pin "11") (pinfunction "A_11") (pintype "input"))
      (node (ref "R24") (pin "1") (pinfunction "1_1") (pintype "passive"))
    )
    (net (code "282") (name "SDF1") (class "Default")
      (node (ref "A40") (pin "8") (pinfunction "8_8") (pintype "passive"))
      (node (ref "IC14") (pin "12") (pinfunction "B_12") (pintype "input"))
      (node (ref "R25") (pin "1") (pinfunction "1_1") (pintype "passive"))
    )
    (net (code "283") (name "SDF2") (class "Default")
      (node (ref "A40") (pin "10") (pinfunction "10_10") (pintype "passive"))
      (node (ref "IC14") (pin "13") (pinfunction "C_13") (pintype "input"))
      (node (ref "R26") (pin "1") (pinfunction "1_1") (pintype "passive"))
    )
    (net (code "284") (name "SI") (class "Default")
      (node (ref "B40") (pin "32") (pinfunction "32_32") (pintype "passive"))
      (node (ref "IC18") (pin "12") (pinfunction "B_12") (pintype "input"))
      (node (ref "R49") (pin "1") (pinfunction "1_1") (pintype "passive"))
    )
    (net (code "285") (name "SIF0") (class "Default")
      (node (ref "A40") (pin "12") (pinfunction "12_12") (pintype "passive"))
      (node (ref "IC14") (pin "14") (pinfunction "D_14") (pintype "input"))
      (node (ref "R27") (pin "1") (pinfunction "1_1") (pintype "passive"))
    )
    (net (code "286") (name "SIF1") (class "Default")
      (node (ref "A40") (pin "14") (pinfunction "14_14") (pintype "passive"))
      (node (ref "IC14") (pin "3") (pinfunction "E_3") (pintype "input"))
      (node (ref "R28") (pin "1") (pinfunction "1_1") (pintype "passive"))
    )
    (net (code "287") (name "SIF2") (class "Default")
      (node (ref "A40") (pin "16") (pinfunction "16_16") (pintype "passive"))
      (node (ref "IC14") (pin "4") (pinfunction "F_4") (pintype "input"))
      (node (ref "R29") (pin "1") (pinfunction "1_1") (pintype "passive"))
    )
    (net (code "288") (name "SLOT1-CS#") (class "Default")
      (node (ref "SLOT1") (pin "37") (pinfunction "37_37") (pintype "passive"))
      (node (ref "XESS") (pin "18") (pinfunction "E15_18") (pintype "bidirectional"))
    )
    (net (code "289") (name "SLOT1-IRQ") (class "Default")
      (node (ref "R21") (pin "1") (pinfunction "1_1") (pintype "passive"))
      (node (ref "XESS") (pin "84") (pinfunction "J16_84") (pintype "bidirectional"))
    )
    (net (code "290") (name "SLOT2-CS#") (class "Default")
      (node (ref "SLOT2") (pin "37") (pinfunction "37_37") (pintype "passive"))
      (node (ref "XESS") (pin "19") (pinfunction "D16_19") (pintype "bidirectional"))
    )
    (net (code "291") (name "SLOT2-IRQ") (class "Default")
      (node (ref "R22") (pin "1") (pinfunction "1_1") (pintype "passive"))
      (node (ref "XESS") (pin "83") (pinfunction "J14_83") (pintype "bidirectional"))
    )
    (net (code "292") (name "SR0") (class "Default")
      (node (ref "A40") (pin "18") (pinfunction "18_18") (pintype "passive"))
      (node (ref "IC14") (pin "5") (pinfunction "G_5") (pintype "input"))
      (node (ref "R30") (pin "1") (pinfunction "1_1") (pintype "passive"))
    )
    (net (code "293") (name "SR1") (class "Default")
      (node (ref "A40") (pin "20") (pinfunction "20_20") (pintype "passive"))
      (node (ref "IC14") (pin "6") (pinfunction "H_6") (pintype "input"))
      (node (ref "R31") (pin "1") (pinfunction "1_1") (pintype "passive"))
    )
    (net (code "294") (name "SR2") (class "Default")
      (node (ref "A40") (pin "26") (pinfunction "26_26") (pintype "passive"))
      (node (ref "IC15") (pin "11") (pinfunction "A_11") (pintype "input"))
      (node (ref "R32") (pin "1") (pinfunction "1_1") (pintype "passive"))
    )
    (net (code "295") (name "SR3") (class "Default")
      (node (ref "A40") (pin "28") (pinfunction "28_28") (pintype "passive"))
      (node (ref "IC15") (pin "12") (pinfunction "B_12") (pintype "input"))
      (node (ref "R33") (pin "1") (pinfunction "1_1") (pintype "passive"))
    )
    (net (code "296") (name "SR4") (class "Default")
      (node (ref "A40") (pin "30") (pinfunction "30_30") (pintype "passive"))
      (node (ref "IC15") (pin "13") (pinfunction "C_13") (pintype "input"))
      (node (ref "R34") (pin "1") (pinfunction "1_1") (pintype "passive"))
    )
    (net (code "297") (name "SR5") (class "Default")
      (node (ref "A40") (pin "34") (pinfunction "34_34") (pintype "passive"))
      (node (ref "IC15") (pin "14") (pinfunction "D_14") (pintype "input"))
      (node (ref "R35") (pin "1") (pinfunction "1_1") (pintype "passive"))
    )
    (net (code "298") (name "SR6") (class "Default")
      (node (ref "A40") (pin "32") (pinfunction "32_32") (pintype "passive"))
      (node (ref "IC15") (pin "3") (pinfunction "E_3") (pintype "input"))
      (node (ref "R36") (pin "1") (pinfunction "1_1") (pintype "passive"))
    )
    (net (code "299") (name "SR7") (class "Default")
      (node (ref "B40") (pin "6") (pinfunction "6_6") (pintype "passive"))
      (node (ref "IC15") (pin "4") (pinfunction "F_4") (pintype "input"))
      (node (ref "R37") (pin "1") (pinfunction "1_1") (pintype "passive"))
    )
    (net (code "300") (name "SR8") (class "Default")
      (node (ref "B40") (pin "8") (pinfunction "8_8") (pintype "passive"))
      (node (ref "IC15") (pin "5") (pinfunction "G_5") (pintype "input"))
      (node (ref "R38") (pin "1") (pinfunction "1_1") (pintype "passive"))
    )
    (net (code "301") (name "SR9") (class "Default")
      (node (ref "B40") (pin "10") (pinfunction "10_10") (pintype "passive"))
      (node (ref "IC15") (pin "6") (pinfunction "H_6") (pintype "input"))
      (node (ref "R39") (pin "1") (pinfunction "1_1") (pintype "passive"))
    )
    (net (code "302") (name "SR10") (class "Default")
      (node (ref "B40") (pin "12") (pinfunction "12_12") (pintype "passive"))
      (node (ref "IC2") (pin "11") (pinfunction "A_11") (pintype "input"))
      (node (ref "R40") (pin "1") (pinfunction "1_1") (pintype "passive"))
    )
    (net (code "303") (name "SR11") (class "Default")
      (node (ref "B40") (pin "14") (pinfunction "14_14") (pintype "passive"))
      (node (ref "IC2") (pin "12") (pinfunction "B_12") (pintype "input"))
      (node (ref "R41") (pin "1") (pinfunction "1_1") (pintype "passive"))
    )
    (net (code "304") (name "SS") (class "Default")
      (node (ref "B40") (pin "34") (pinfunction "34_34") (pintype "passive"))
      (node (ref "IC18") (pin "11") (pinfunction "A_11") (pintype "input"))
      (node (ref "R48") (pin "1") (pinfunction "1_1") (pintype "passive"))
    )
    (net (code "305") (name "START") (class "Default")
      (node (ref "B40") (pin "16") (pinfunction "16_16") (pintype "passive"))
      (node (ref "IC2") (pin "13") (pinfunction "C_13") (pintype "input"))
      (node (ref "R42") (pin "1") (pinfunction "1_1") (pintype "passive"))
    )
    (net (code "306") (name "STOP") (class "Default")
      (node (ref "B40") (pin "30") (pinfunction "30_30") (pintype "passive"))
      (node (ref "IC2") (pin "6") (pinfunction "H_6") (pintype "input"))
      (node (ref "R47") (pin "1") (pinfunction "1_1") (pintype "passive"))
    )
    (net (code "307") (name "TAD") (class "Default")
      (node (ref "D40") (pin "4") (pinfunction "4_4") (pintype "passive"))
      (node (ref "R53") (pin "2") (pinfunction "2_2") (pintype "passive"))
    )
    (net (code "308") (name "TXD") (class "Default")
      (node (ref "IC3") (pin "13") (pinfunction "R1IN_13") (pintype "input"))
      (node (ref "IC3") (pin "14") (pinfunction "T1OUT_14") (pintype "output"))
      (node (ref "RS-232") (pin "2") (pinfunction "2_2") (pintype "passive"))
      (node (ref "X1") (pin "2") (pinfunction "F_2") (pintype "passive"))
    )
    (net (code "309") (name "VCC") (class "Default")
      (node (ref "+V1") (pin "1") (pinfunction "1_1") (pintype "passive"))
      (node (ref "+V2") (pin "1") (pinfunction "1_1") (pintype "passive"))
      (node (ref "+V3") (pin "1") (pinfunction "1_1") (pintype "passive"))
      (node (ref "+V4") (pin "1") (pinfunction "1_1") (pintype "passive"))
      (node (ref "5V") (pin "1") (pinfunction "1_1") (pintype "passive"))
      (node (ref "C1") (pin "1") (pinfunction "1_1") (pintype "passive"))
      (node (ref "C10") (pin "1") (pinfunction "1_1") (pintype "passive"))
      (node (ref "C11") (pin "1") (pinfunction "1_1") (pintype "passive"))
      (node (ref "C12") (pin "1") (pinfunction "1_1") (pintype "passive"))
      (node (ref "C13") (pin "1") (pinfunction "1_1") (pintype "passive"))
      (node (ref "C14") (pin "1") (pinfunction "1_1") (pintype "passive"))
      (node (ref "C15") (pin "1") (pinfunction "1_1") (pintype "passive"))
      (node (ref "C16") (pin "1") (pinfunction "1_1") (pintype "passive"))
      (node (ref "C17") (pin "1") (pinfunction "1_1") (pintype "passive"))
      (node (ref "C18") (pin "1") (pinfunction "1_1") (pintype "passive"))
      (node (ref "C19") (pin "1") (pinfunction "1_1") (pintype "passive"))
      (node (ref "C20") (pin "1") (pinfunction "1_1") (pintype "passive"))
      (node (ref "C21") (pin "1") (pinfunction "1_1") (pintype "passive"))
      (node (ref "C22") (pin "1") (pinfunction "1_1") (pintype "passive"))
      (node (ref "C23") (pin "1") (pinfunction "1_1") (pintype "passive"))
      (node (ref "C24") (pin "1") (pinfunction "1_1") (pintype "passive"))
      (node (ref "C6") (pin "1") (pinfunction "1_1") (pintype "passive"))
      (node (ref "C7") (pin "1") (pinfunction "1_1") (pintype "passive"))
      (node (ref "C8") (pin "1") (pinfunction "1_1") (pintype "passive"))
      (node (ref "C9") (pin "1") (pinfunction "1_1") (pintype "passive"))
      (node (ref "IC19") (pin "10") (pinfunction "I1_10") (pintype "input"))
      (node (ref "IC19") (pin "12") (pinfunction "I0_12") (pintype "input"))
      (node (ref "IC19") (pin "13") (pinfunction "I1_13") (pintype "input"))
      (node (ref "IC19") (pin "9") (pinfunction "I0_9") (pintype "input"))
      (node (ref "J1") (pin "4") (pinfunction "4_4") (pintype "passive"))
      (node (ref "R10") (pin "1") (pinfunction "1_1") (pintype "passive"))
      (node (ref "R24") (pin "2") (pinfunction "2_2") (pintype "passive"))
      (node (ref "R25") (pin "2") (pinfunction "2_2") (pintype "passive"))
      (node (ref "R26") (pin "2") (pinfunction "2_2") (pintype "passive"))
      (node (ref "R27") (pin "2") (pinfunction "2_2") (pintype "passive"))
      (node (ref "R28") (pin "2") (pinfunction "2_2") (pintype "passive"))
      (node (ref "R29") (pin "2") (pinfunction "2_2") (pintype "passive"))
      (node (ref "R30") (pin "2") (pinfunction "2_2") (pintype "passive"))
      (node (ref "R31") (pin "2") (pinfunction "2_2") (pintype "passive"))
      (node (ref "R32") (pin "2") (pinfunction "2_2") (pintype "passive"))
      (node (ref "R33") (pin "2") (pinfunction "2_2") (pintype "passive"))
      (node (ref "R34") (pin "2") (pinfunction "2_2") (pintype "passive"))
      (node (ref "R35") (pin "2") (pinfunction "2_2") (pintype "passive"))
      (node (ref "R36") (pin "2") (pinfunction "2_2") (pintype "passive"))
      (node (ref "R37") (pin "2") (pinfunction "2_2") (pintype "passive"))
      (node (ref "R38") (pin "2") (pinfunction "2_2") (pintype "passive"))
      (node (ref "R39") (pin "2") (pinfunction "2_2") (pintype "passive"))
      (node (ref "R40") (pin "2") (pinfunction "2_2") (pintype "passive"))
      (node (ref "R41") (pin "2") (pinfunction "2_2") (pintype "passive"))
      (node (ref "R42") (pin "2") (pinfunction "2_2") (pintype "passive"))
      (node (ref "R43") (pin "2") (pinfunction "2_2") (pintype "passive"))
      (node (ref "R44") (pin "2") (pinfunction "2_2") (pintype "passive"))
      (node (ref "R45") (pin "2") (pinfunction "2_2") (pintype "passive"))
      (node (ref "R46") (pin "2") (pinfunction "2_2") (pintype "passive"))
      (node (ref "R47") (pin "2") (pinfunction "2_2") (pintype "passive"))
      (node (ref "R48") (pin "2") (pinfunction "2_2") (pintype "passive"))
      (node (ref "R49") (pin "2") (pinfunction "2_2") (pintype "passive"))
      (node (ref "R50") (pin "1") (pinfunction "1_1") (pintype "passive"))
      (node (ref "R6") (pin "1") (pinfunction "1_1") (pintype "passive"))
      (node (ref "R7") (pin "1") (pinfunction "1_1") (pintype "passive"))
      (node (ref "R8") (pin "1") (pinfunction "1_1") (pintype "passive"))
      (node (ref "R9") (pin "1") (pinfunction "1_1") (pintype "passive"))
    )
    (net (code "310") (name "VDD") (class "Default")
      (node (ref "3.3V") (pin "2") (pinfunction "2_2") (pintype "passive"))
      (node (ref "J4") (pin "4") (pinfunction "VDD_4") (pintype "power_in"))
    )
    (net (code "311") (name "VSS") (class "Default")
      (node (ref "J3") (pin "1") (pinfunction "1_1") (pintype "passive"))
      (node (ref "J4") (pin "3") (pinfunction "VSS_3") (pintype "power_in"))
      (node (ref "J4") (pin "6") (pinfunction "VSS_6") (pintype "power_in"))
    )
    (net (code "312") (name "WC") (class "Default")
      (node (ref "D40") (pin "30") (pinfunction "30_30") (pintype "passive"))
      (node (ref "R64") (pin "2") (pinfunction "2_2") (pintype "passive"))
    )
    (net (code "313") (name "unconnected-(A40-Pad1)") (class "Default")
      (node (ref "A40") (pin "1") (pinfunction "1_1") (pintype "passive"))
    )
    (net (code "314") (name "unconnected-(A40-Pad2)") (class "Default")
      (node (ref "A40") (pin "2") (pinfunction "2_2") (pintype "passive"))
    )
    (net (code "315") (name "unconnected-(A40-Pad3)") (class "Default")
      (node (ref "A40") (pin "3") (pinfunction "3_3") (pintype "passive"))
    )
    (net (code "316") (name "unconnected-(A40-Pad5)") (class "Default")
      (node (ref "A40") (pin "5") (pinfunction "5_5") (pintype "passive"))
    )
    (net (code "317") (name "unconnected-(A40-Pad7)") (class "Default")
      (node (ref "A40") (pin "7") (pinfunction "7_7") (pintype "passive"))
    )
    (net (code "318") (name "unconnected-(A40-Pad9)") (class "Default")
      (node (ref "A40") (pin "9") (pinfunction "9_9") (pintype "passive"))
    )
    (net (code "319") (name "unconnected-(A40-Pad11)") (class "Default")
      (node (ref "A40") (pin "11") (pinfunction "11_11") (pintype "passive"))
    )
    (net (code "320") (name "unconnected-(A40-Pad13)") (class "Default")
      (node (ref "A40") (pin "13") (pinfunction "13_13") (pintype "passive"))
    )
    (net (code "321") (name "unconnected-(A40-Pad15)") (class "Default")
      (node (ref "A40") (pin "15") (pinfunction "15_15") (pintype "passive"))
    )
    (net (code "322") (name "unconnected-(A40-Pad17)") (class "Default")
      (node (ref "A40") (pin "17") (pinfunction "17_17") (pintype "passive"))
    )
    (net (code "323") (name "unconnected-(A40-Pad19)") (class "Default")
      (node (ref "A40") (pin "19") (pinfunction "19_19") (pintype "passive"))
    )
    (net (code "324") (name "unconnected-(A40-Pad21)") (class "Default")
      (node (ref "A40") (pin "21") (pinfunction "21_21") (pintype "passive"))
    )
    (net (code "325") (name "unconnected-(A40-Pad22)") (class "Default")
      (node (ref "A40") (pin "22") (pinfunction "22_22") (pintype "passive"))
    )
    (net (code "326") (name "unconnected-(A40-Pad23)") (class "Default")
      (node (ref "A40") (pin "23") (pinfunction "23_23") (pintype "passive"))
    )
    (net (code "327") (name "unconnected-(A40-Pad24)") (class "Default")
      (node (ref "A40") (pin "24") (pinfunction "24_24") (pintype "passive"))
    )
    (net (code "328") (name "unconnected-(A40-Pad25)") (class "Default")
      (node (ref "A40") (pin "25") (pinfunction "25_25") (pintype "passive"))
    )
    (net (code "329") (name "unconnected-(A40-Pad27)") (class "Default")
      (node (ref "A40") (pin "27") (pinfunction "27_27") (pintype "passive"))
    )
    (net (code "330") (name "unconnected-(A40-Pad29)") (class "Default")
      (node (ref "A40") (pin "29") (pinfunction "29_29") (pintype "passive"))
    )
    (net (code "331") (name "unconnected-(A40-Pad31)") (class "Default")
      (node (ref "A40") (pin "31") (pinfunction "31_31") (pintype "passive"))
    )
    (net (code "332") (name "unconnected-(A40-Pad33)") (class "Default")
      (node (ref "A40") (pin "33") (pinfunction "33_33") (pintype "passive"))
    )
    (net (code "333") (name "unconnected-(B40-Pad1)") (class "Default")
      (node (ref "B40") (pin "1") (pinfunction "1_1") (pintype "passive"))
    )
    (net (code "334") (name "unconnected-(B40-Pad2)") (class "Default")
      (node (ref "B40") (pin "2") (pinfunction "2_2") (pintype "passive"))
    )
    (net (code "335") (name "unconnected-(B40-Pad3)") (class "Default")
      (node (ref "B40") (pin "3") (pinfunction "3_3") (pintype "passive"))
    )
    (net (code "336") (name "unconnected-(B40-Pad5)") (class "Default")
      (node (ref "B40") (pin "5") (pinfunction "5_5") (pintype "passive"))
    )
    (net (code "337") (name "unconnected-(B40-Pad7)") (class "Default")
      (node (ref "B40") (pin "7") (pinfunction "7_7") (pintype "passive"))
    )
    (net (code "338") (name "unconnected-(B40-Pad9)") (class "Default")
      (node (ref "B40") (pin "9") (pinfunction "9_9") (pintype "passive"))
    )
    (net (code "339") (name "unconnected-(B40-Pad11)") (class "Default")
      (node (ref "B40") (pin "11") (pinfunction "11_11") (pintype "passive"))
    )
    (net (code "340") (name "unconnected-(B40-Pad13)") (class "Default")
      (node (ref "B40") (pin "13") (pinfunction "13_13") (pintype "passive"))
    )
    (net (code "341") (name "unconnected-(B40-Pad15)") (class "Default")
      (node (ref "B40") (pin "15") (pinfunction "15_15") (pintype "passive"))
    )
    (net (code "342") (name "unconnected-(B40-Pad17)") (class "Default")
      (node (ref "B40") (pin "17") (pinfunction "17_17") (pintype "passive"))
    )
    (net (code "343") (name "unconnected-(B40-Pad19)") (class "Default")
      (node (ref "B40") (pin "19") (pinfunction "19_19") (pintype "passive"))
    )
    (net (code "344") (name "unconnected-(B40-Pad21)") (class "Default")
      (node (ref "B40") (pin "21") (pinfunction "21_21") (pintype "passive"))
    )
    (net (code "345") (name "unconnected-(B40-Pad22)") (class "Default")
      (node (ref "B40") (pin "22") (pinfunction "22_22") (pintype "passive"))
    )
    (net (code "346") (name "unconnected-(B40-Pad23)") (class "Default")
      (node (ref "B40") (pin "23") (pinfunction "23_23") (pintype "passive"))
    )
    (net (code "347") (name "unconnected-(B40-Pad24)") (class "Default")
      (node (ref "B40") (pin "24") (pinfunction "24_24") (pintype "passive"))
    )
    (net (code "348") (name "unconnected-(B40-Pad25)") (class "Default")
      (node (ref "B40") (pin "25") (pinfunction "25_25") (pintype "passive"))
    )
    (net (code "349") (name "unconnected-(B40-Pad27)") (class "Default")
      (node (ref "B40") (pin "27") (pinfunction "27_27") (pintype "passive"))
    )
    (net (code "350") (name "unconnected-(B40-Pad29)") (class "Default")
      (node (ref "B40") (pin "29") (pinfunction "29_29") (pintype "passive"))
    )
    (net (code "351") (name "unconnected-(B40-Pad31)") (class "Default")
      (node (ref "B40") (pin "31") (pinfunction "31_31") (pintype "passive"))
    )
    (net (code "352") (name "unconnected-(B40-Pad33)") (class "Default")
      (node (ref "B40") (pin "33") (pinfunction "33_33") (pintype "passive"))
    )
    (net (code "353") (name "unconnected-(C40-Pad3)") (class "Default")
      (node (ref "C40") (pin "3") (pinfunction "3_3") (pintype "passive"))
    )
    (net (code "354") (name "unconnected-(C40-Pad4)") (class "Default")
      (node (ref "C40") (pin "4") (pinfunction "4_4") (pintype "passive"))
    )
    (net (code "355") (name "unconnected-(C40-Pad5)") (class "Default")
      (node (ref "C40") (pin "5") (pinfunction "5_5") (pintype "passive"))
    )
    (net (code "356") (name "unconnected-(C40-Pad6)") (class "Default")
      (node (ref "C40") (pin "6") (pinfunction "6_6") (pintype "passive"))
    )
    (net (code "357") (name "unconnected-(C40-Pad7)") (class "Default")
      (node (ref "C40") (pin "7") (pinfunction "7_7") (pintype "passive"))
    )
    (net (code "358") (name "unconnected-(C40-Pad8)") (class "Default")
      (node (ref "C40") (pin "8") (pinfunction "8_8") (pintype "passive"))
    )
    (net (code "359") (name "unconnected-(C40-Pad13)") (class "Default")
      (node (ref "C40") (pin "13") (pinfunction "13_13") (pintype "passive"))
    )
    (net (code "360") (name "unconnected-(C40-Pad14)") (class "Default")
      (node (ref "C40") (pin "14") (pinfunction "14_14") (pintype "passive"))
    )
    (net (code "361") (name "unconnected-(C40-Pad15)") (class "Default")
      (node (ref "C40") (pin "15") (pinfunction "15_15") (pintype "passive"))
    )
    (net (code "362") (name "unconnected-(C40-Pad16)") (class "Default")
      (node (ref "C40") (pin "16") (pinfunction "16_16") (pintype "passive"))
    )
    (net (code "363") (name "unconnected-(C40-Pad21)") (class "Default")
      (node (ref "C40") (pin "21") (pinfunction "21_21") (pintype "passive"))
    )
    (net (code "364") (name "unconnected-(C40-Pad22)") (class "Default")
      (node (ref "C40") (pin "22") (pinfunction "22_22") (pintype "passive"))
    )
    (net (code "365") (name "unconnected-(C40-Pad26)") (class "Default")
      (node (ref "C40") (pin "26") (pinfunction "26_26") (pintype "passive"))
    )
    (net (code "366") (name "unconnected-(C40-Pad27)") (class "Default")
      (node (ref "C40") (pin "27") (pinfunction "27_27") (pintype "passive"))
    )
    (net (code "367") (name "unconnected-(C40-Pad29)") (class "Default")
      (node (ref "C40") (pin "29") (pinfunction "29_29") (pintype "passive"))
    )
    (net (code "368") (name "unconnected-(C40-Pad30)") (class "Default")
      (node (ref "C40") (pin "30") (pinfunction "30_30") (pintype "passive"))
    )
    (net (code "369") (name "unconnected-(C40-Pad31)") (class "Default")
      (node (ref "C40") (pin "31") (pinfunction "31_31") (pintype "passive"))
    )
    (net (code "370") (name "unconnected-(C40-Pad32)") (class "Default")
      (node (ref "C40") (pin "32") (pinfunction "32_32") (pintype "passive"))
    )
    (net (code "371") (name "unconnected-(CONFIGSW-Pad7)") (class "Default")
      (node (ref "CONFIGSW") (pin "7") (pinfunction "7_7") (pintype "passive"))
    )
    (net (code "372") (name "unconnected-(CONFIGSW-Pad8)") (class "Default")
      (node (ref "CONFIGSW") (pin "8") (pinfunction "8_8") (pintype "passive"))
    )
    (net (code "373") (name "unconnected-(CONFIGSW-Pad9)") (class "Default")
      (node (ref "CONFIGSW") (pin "9") (pinfunction "9_9") (pintype "passive"))
    )
    (net (code "374") (name "unconnected-(D40-Pad1)") (class "Default")
      (node (ref "D40") (pin "1") (pinfunction "1_1") (pintype "passive"))
    )
    (net (code "375") (name "unconnected-(D40-Pad3)") (class "Default")
      (node (ref "D40") (pin "3") (pinfunction "3_3") (pintype "passive"))
    )
    (net (code "376") (name "unconnected-(D40-Pad5)") (class "Default")
      (node (ref "D40") (pin "5") (pinfunction "5_5") (pintype "passive"))
    )
    (net (code "377") (name "unconnected-(D40-Pad7)") (class "Default")
      (node (ref "D40") (pin "7") (pinfunction "7_7") (pintype "passive"))
    )
    (net (code "378") (name "unconnected-(D40-Pad9)") (class "Default")
      (node (ref "D40") (pin "9") (pinfunction "9_9") (pintype "passive"))
    )
    (net (code "379") (name "unconnected-(D40-Pad11)") (class "Default")
      (node (ref "D40") (pin "11") (pinfunction "11_11") (pintype "passive"))
    )
    (net (code "380") (name "unconnected-(D40-Pad13)") (class "Default")
      (node (ref "D40") (pin "13") (pinfunction "13_13") (pintype "passive"))
    )
    (net (code "381") (name "unconnected-(D40-Pad14)") (class "Default")
      (node (ref "D40") (pin "14") (pinfunction "14_14") (pintype "passive"))
    )
    (net (code "382") (name "unconnected-(D40-Pad15)") (class "Default")
      (node (ref "D40") (pin "15") (pinfunction "15_15") (pintype "passive"))
    )
    (net (code "383") (name "unconnected-(D40-Pad21)") (class "Default")
      (node (ref "D40") (pin "21") (pinfunction "21_21") (pintype "passive"))
    )
    (net (code "384") (name "unconnected-(D40-Pad25)") (class "Default")
      (node (ref "D40") (pin "25") (pinfunction "25_25") (pintype "passive"))
    )
    (net (code "385") (name "unconnected-(D40-Pad27)") (class "Default")
      (node (ref "D40") (pin "27") (pinfunction "27_27") (pintype "passive"))
    )
    (net (code "386") (name "unconnected-(D40-Pad29)") (class "Default")
      (node (ref "D40") (pin "29") (pinfunction "29_29") (pintype "passive"))
    )
    (net (code "387") (name "unconnected-(IC2A-~{QH}-Pad7)") (class "Default")
      (node (ref "IC2") (pin "7") (pinfunction "~{QH}_7") (pintype "output"))
    )
    (net (code "388") (name "unconnected-(IC3A-R1OUT-Pad12)") (class "Default")
      (node (ref "IC3") (pin "12") (pinfunction "R1OUT_12") (pintype "output"))
    )
    (net (code "389") (name "unconnected-(IC4A-QE-Pad4)") (class "Default")
      (node (ref "IC4") (pin "4") (pinfunction "QE_4") (pintype "tri_state"))
    )
    (net (code "390") (name "unconnected-(IC4A-QF-Pad5)") (class "Default")
      (node (ref "IC4") (pin "5") (pinfunction "QF_5") (pintype "tri_state"))
    )
    (net (code "391") (name "unconnected-(IC4A-QG-Pad6)") (class "Default")
      (node (ref "IC4") (pin "6") (pinfunction "QG_6") (pintype "tri_state"))
    )
    (net (code "392") (name "unconnected-(IC4A-QH-Pad7)") (class "Default")
      (node (ref "IC4") (pin "7") (pinfunction "QH_7") (pintype "tri_state"))
    )
    (net (code "393") (name "unconnected-(IC8A-QG-Pad6)") (class "Default")
      (node (ref "IC8") (pin "6") (pinfunction "QG_6") (pintype "tri_state"))
    )
    (net (code "394") (name "unconnected-(IC8A-QH-Pad7)") (class "Default")
      (node (ref "IC8") (pin "7") (pinfunction "QH_7") (pintype "tri_state"))
    )
    (net (code "395") (name "unconnected-(IC12A-QG-Pad6)") (class "Default")
      (node (ref "IC12") (pin "6") (pinfunction "QG_6") (pintype "tri_state"))
    )
    (net (code "396") (name "unconnected-(IC14A-~{QH}-Pad7)") (class "Default")
      (node (ref "IC14") (pin "7") (pinfunction "~{QH}_7") (pintype "output"))
    )
    (net (code "397") (name "unconnected-(IC15A-~{QH}-Pad7)") (class "Default")
      (node (ref "IC15") (pin "7") (pinfunction "~{QH}_7") (pintype "output"))
    )
    (net (code "398") (name "unconnected-(IC18A-~{QH}-Pad7)") (class "Default")
      (node (ref "IC18") (pin "7") (pinfunction "~{QH}_7") (pintype "output"))
    )
    (net (code "399") (name "unconnected-(IC19C-O-Pad8)") (class "Default")
      (node (ref "IC19") (pin "8") (pinfunction "O_8") (pintype "output"))
    )
    (net (code "400") (name "unconnected-(IC19D-O-Pad11)") (class "Default")
      (node (ref "IC19") (pin "11") (pinfunction "O_11") (pintype "output"))
    )
    (net (code "401") (name "unconnected-(IDE-Pad20)") (class "Default")
      (node (ref "IDE") (pin "20") (pinfunction "20_20") (pintype "passive"))
    )
    (net (code "402") (name "unconnected-(IDE-Pad32)") (class "Default")
      (node (ref "IDE") (pin "32") (pinfunction "32_32") (pintype "passive"))
    )
    (net (code "403") (name "unconnected-(IDE-Pad34)") (class "Default")
      (node (ref "IDE") (pin "34") (pinfunction "34_34") (pintype "passive"))
    )
    (net (code "404") (name "unconnected-(IDE-Pad39)") (class "Default")
      (node (ref "IDE") (pin "39") (pinfunction "39_39") (pintype "passive"))
    )
    (net (code "405") (name "unconnected-(RS-232-Pad1)") (class "Default")
      (node (ref "RS-232") (pin "1") (pinfunction "1_1") (pintype "passive"))
    )
    (net (code "406") (name "unconnected-(SLOT1-Pad34)") (class "Default")
      (node (ref "SLOT1") (pin "34") (pinfunction "34_34") (pintype "passive"))
    )
    (net (code "407") (name "unconnected-(SLOT2-Pad34)") (class "Default")
      (node (ref "SLOT2") (pin "34") (pinfunction "34_34") (pintype "passive"))
    )
    (net (code "408") (name "unconnected-(SV1-Pad2)") (class "Default")
      (node (ref "SV1") (pin "2") (pinfunction "2_2") (pintype "passive"))
    )
    (net (code "409") (name "unconnected-(SV1-Pad4)") (class "Default")
      (node (ref "SV1") (pin "4") (pinfunction "4_4") (pintype "passive"))
    )
    (net (code "410") (name "unconnected-(SV2-Pad2)") (class "Default")
      (node (ref "SV2") (pin "2") (pinfunction "2_2") (pintype "passive"))
    )
    (net (code "411") (name "unconnected-(SV2-Pad4)") (class "Default")
      (node (ref "SV2") (pin "4") (pinfunction "4_4") (pintype "passive"))
    )
    (net (code "412") (name "unconnected-(XESS-BSY-Pad17)") (class "Default")
      (node (ref "XESS") (pin "17") (pinfunction "BSY_17") (pintype "bidirectional"))
    )
    (net (code "413") (name "unconnected-(XESS-CLKB-Pad11)") (class "Default")
      (node (ref "XESS") (pin "11") (pinfunction "CLKB_11") (pintype "bidirectional"))
    )
    (net (code "414") (name "unconnected-(XESS-CLKC-Pad64)") (class "Default")
      (node (ref "XESS") (pin "64") (pinfunction "CLKC_64") (pintype "bidirectional"))
    )
    (net (code "415") (name "unconnected-(XESS-CS#-Pad15)") (class "Default")
      (node (ref "XESS") (pin "15") (pinfunction "CS#_15") (pintype "bidirectional"))
    )
    (net (code "416") (name "unconnected-(XESS-D1-Pad25)") (class "Default")
      (node (ref "XESS") (pin "25") (pinfunction "D1_25") (pintype "bidirectional"))
    )
    (net (code "417") (name "unconnected-(XESS-E14-Pad20)") (class "Default")
      (node (ref "XESS") (pin "20") (pinfunction "E14_20") (pintype "bidirectional"))
    )
    (net (code "418") (name "unconnected-(XESS-G13-Pad9)") (class "Default")
      (node (ref "XESS") (pin "9") (pinfunction "G13_9") (pintype "bidirectional"))
    )
    (net (code "419") (name "unconnected-(XESS-G16-Pad6)") (class "Default")
      (node (ref "XESS") (pin "6") (pinfunction "G16_6") (pintype "bidirectional"))
    )
    (net (code "420") (name "unconnected-(XESS-J3-Pad42)") (class "Default")
      (node (ref "XESS") (pin "42") (pinfunction "J3_42") (pintype "bidirectional"))
    )
    (net (code "421") (name "unconnected-(XESS-J13-Pad82)") (class "Default")
      (node (ref "XESS") (pin "82") (pinfunction "J13_82") (pintype "bidirectional"))
    )
    (net (code "422") (name "unconnected-(XESS-L3-Pad46)") (class "Default")
      (node (ref "XESS") (pin "46") (pinfunction "L3_46") (pintype "bidirectional"))
    )
    (net (code "423") (name "unconnected-(XESS-L15-Pad79)") (class "Default")
      (node (ref "XESS") (pin "79") (pinfunction "L15_79") (pintype "bidirectional"))
    )
    (net (code "424") (name "unconnected-(XESS-M1-Pad47)") (class "Default")
      (node (ref "XESS") (pin "47") (pinfunction "M1_47") (pintype "bidirectional"))
    )
    (net (code "425") (name "unconnected-(XESS-M2-Pad48)") (class "Default")
      (node (ref "XESS") (pin "48") (pinfunction "M2_48") (pintype "bidirectional"))
    )
    (net (code "426") (name "unconnected-(XESS-N15-Pad77)") (class "Default")
      (node (ref "XESS") (pin "77") (pinfunction "N15_77") (pintype "bidirectional"))
    )
    (net (code "427") (name "unconnected-(XESS-P$53-Pad53)") (class "Default")
      (node (ref "XESS") (pin "53") (pinfunction "P$53_53") (pintype "bidirectional"))
    )
    (net (code "428") (name "unconnected-(XESS-P$63-Pad63)") (class "Default")
      (node (ref "XESS") (pin "63") (pinfunction "P$63_63") (pintype "bidirectional"))
    )
    (net (code "429") (name "unconnected-(XESS-P$65-Pad65)") (class "Default")
      (node (ref "XESS") (pin "65") (pinfunction "P$65_65") (pintype "bidirectional"))
    )
    (net (code "430") (name "unconnected-(XESS-P$72-Pad72)") (class "Default")
      (node (ref "XESS") (pin "72") (pinfunction "P$72_72") (pintype "bidirectional"))
    )
    (net (code "431") (name "unconnected-(XESS-P$73-Pad73)") (class "Default")
      (node (ref "XESS") (pin "73") (pinfunction "P$73_73") (pintype "bidirectional"))
    )
    (net (code "432") (name "unconnected-(XESS-P$74-Pad74)") (class "Default")
      (node (ref "XESS") (pin "74") (pinfunction "P$74_74") (pintype "bidirectional"))
    )
    (net (code "433") (name "unconnected-(XESS-P$75-Pad75)") (class "Default")
      (node (ref "XESS") (pin "75") (pinfunction "P$75_75") (pintype "bidirectional"))
    )
    (net (code "434") (name "unconnected-(XESS-P$76-Pad76)") (class "Default")
      (node (ref "XESS") (pin "76") (pinfunction "P$76_76") (pintype "bidirectional"))
    )
    (net (code "435") (name "unconnected-(XESS-PROG#-Pad55)") (class "Default")
      (node (ref "XESS") (pin "55") (pinfunction "PROG#_55") (pintype "bidirectional"))
    )
    (net (code "436") (name "unconnected-(XESS-TCK-Pad16)") (class "Default")
      (node (ref "XESS") (pin "16") (pinfunction "TCK_16") (pintype "bidirectional"))
    )
    (net (code "437") (name "unconnected-(XESS-WR#-Pad30)") (class "Default")
      (node (ref "XESS") (pin "30") (pinfunction "WR#_30") (pintype "bidirectional"))
    )
    (net (code "438") (name "~{3S-LCL}") (class "Default")
      (node (ref "IC17") (pin "11") (pinfunction "A1_11") (pintype "input"))
      (node (ref "XESS") (pin "78") (pinfunction "M15_78") (pintype "bidirectional"))
    )
    (net (code "439") (name "~{3S-SCL}") (class "Default")
      (node (ref "IC17") (pin "8") (pinfunction "A4_8") (pintype "input"))
      (node (ref "XESS") (pin "60") (pinfunction "N3_60") (pintype "bidirectional"))
    )
    (net (code "440") (name "~{LCL}") (class "Default")
      (node (ref "IC1") (pin "10") (pinfunction "SCL_10") (pintype "input"))
      (node (ref "IC10") (pin "10") (pinfunction "SCL_10") (pintype "input"))
      (node (ref "IC11") (pin "10") (pinfunction "SCL_10") (pintype "input"))
      (node (ref "IC12") (pin "10") (pinfunction "SCL_10") (pintype "input"))
      (node (ref "IC13") (pin "10") (pinfunction "SCL_10") (pintype "input"))
      (node (ref "IC16") (pin "10") (pinfunction "SCL_10") (pintype "input"))
      (node (ref "IC17") (pin "9") (pinfunction "Y1_9") (pintype "tri_state"))
      (node (ref "IC4") (pin "10") (pinfunction "SCL_10") (pintype "input"))
      (node (ref "IC5") (pin "10") (pinfunction "SCL_10") (pintype "input"))
      (node (ref "IC6") (pin "10") (pinfunction "SCL_10") (pintype "input"))
      (node (ref "IC7") (pin "10") (pinfunction "SCL_10") (pintype "input"))
      (node (ref "IC8") (pin "10") (pinfunction "SCL_10") (pintype "input"))
      (node (ref "IC9") (pin "10") (pinfunction "SCL_10") (pintype "input"))
      (node (ref "SV1") (pin "6") (pinfunction "6_6") (pintype "passive"))
      (node (ref "SV2") (pin "6") (pinfunction "6_6") (pintype "passive"))
    )
    (net (code "441") (name "~{SCL}") (class "Default")
      (node (ref "IC14") (pin "1") (pinfunction "SH/~{LD}_1") (pintype "input"))
      (node (ref "IC15") (pin "1") (pinfunction "SH/~{LD}_1") (pintype "input"))
      (node (ref "IC17") (pin "12") (pinfunction "Y4_12") (pintype "tri_state"))
      (node (ref "IC18") (pin "1") (pinfunction "SH/~{LD}_1") (pintype "input"))
      (node (ref "IC2") (pin "1") (pinfunction "SH/~{LD}_1") (pintype "input"))
      (node (ref "SV1") (pin "5") (pinfunction "5_5") (pintype "passive"))
      (node (ref "SV2") (pin "5") (pinfunction "5_5") (pintype "passive"))
    )
    (net (code "442") (name "~{SSER}") (class "Default")
      (node (ref "IC17") (pin "13") (pinfunction "A2_13") (pintype "input"))
      (node (ref "IC18") (pin "9") (pinfunction "QH_9") (pintype "output"))
      (node (ref "SV1") (pin "8") (pinfunction "8_8") (pintype "passive"))
      (node (ref "SV2") (pin "8") (pinfunction "8_8") (pintype "passive"))
    )
  )
)
